# Cing_MainBoard.net
KiCad netlist of a schematic drawn in EAGLE
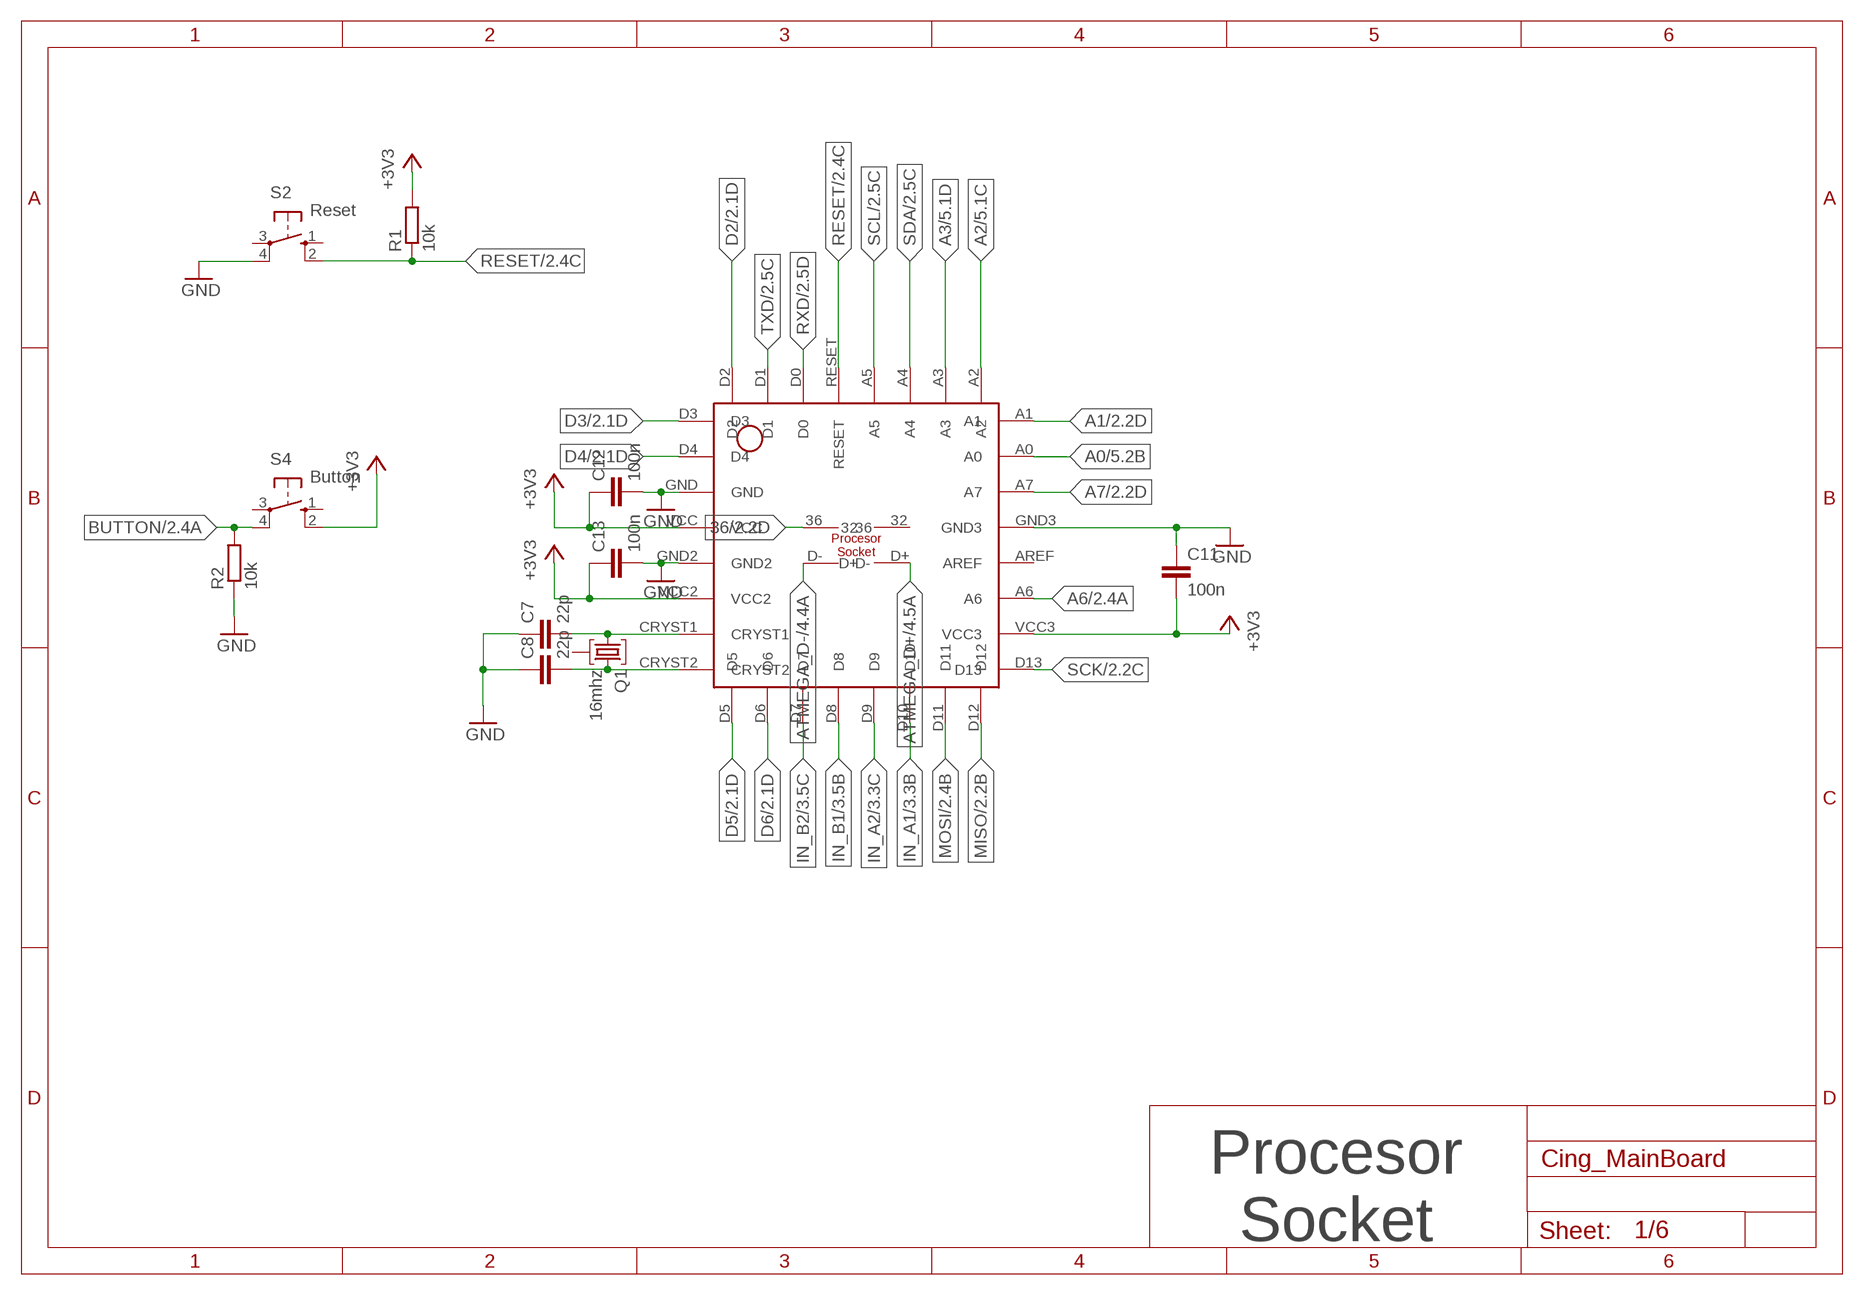
[diagram p0: schematic, sheet 1]
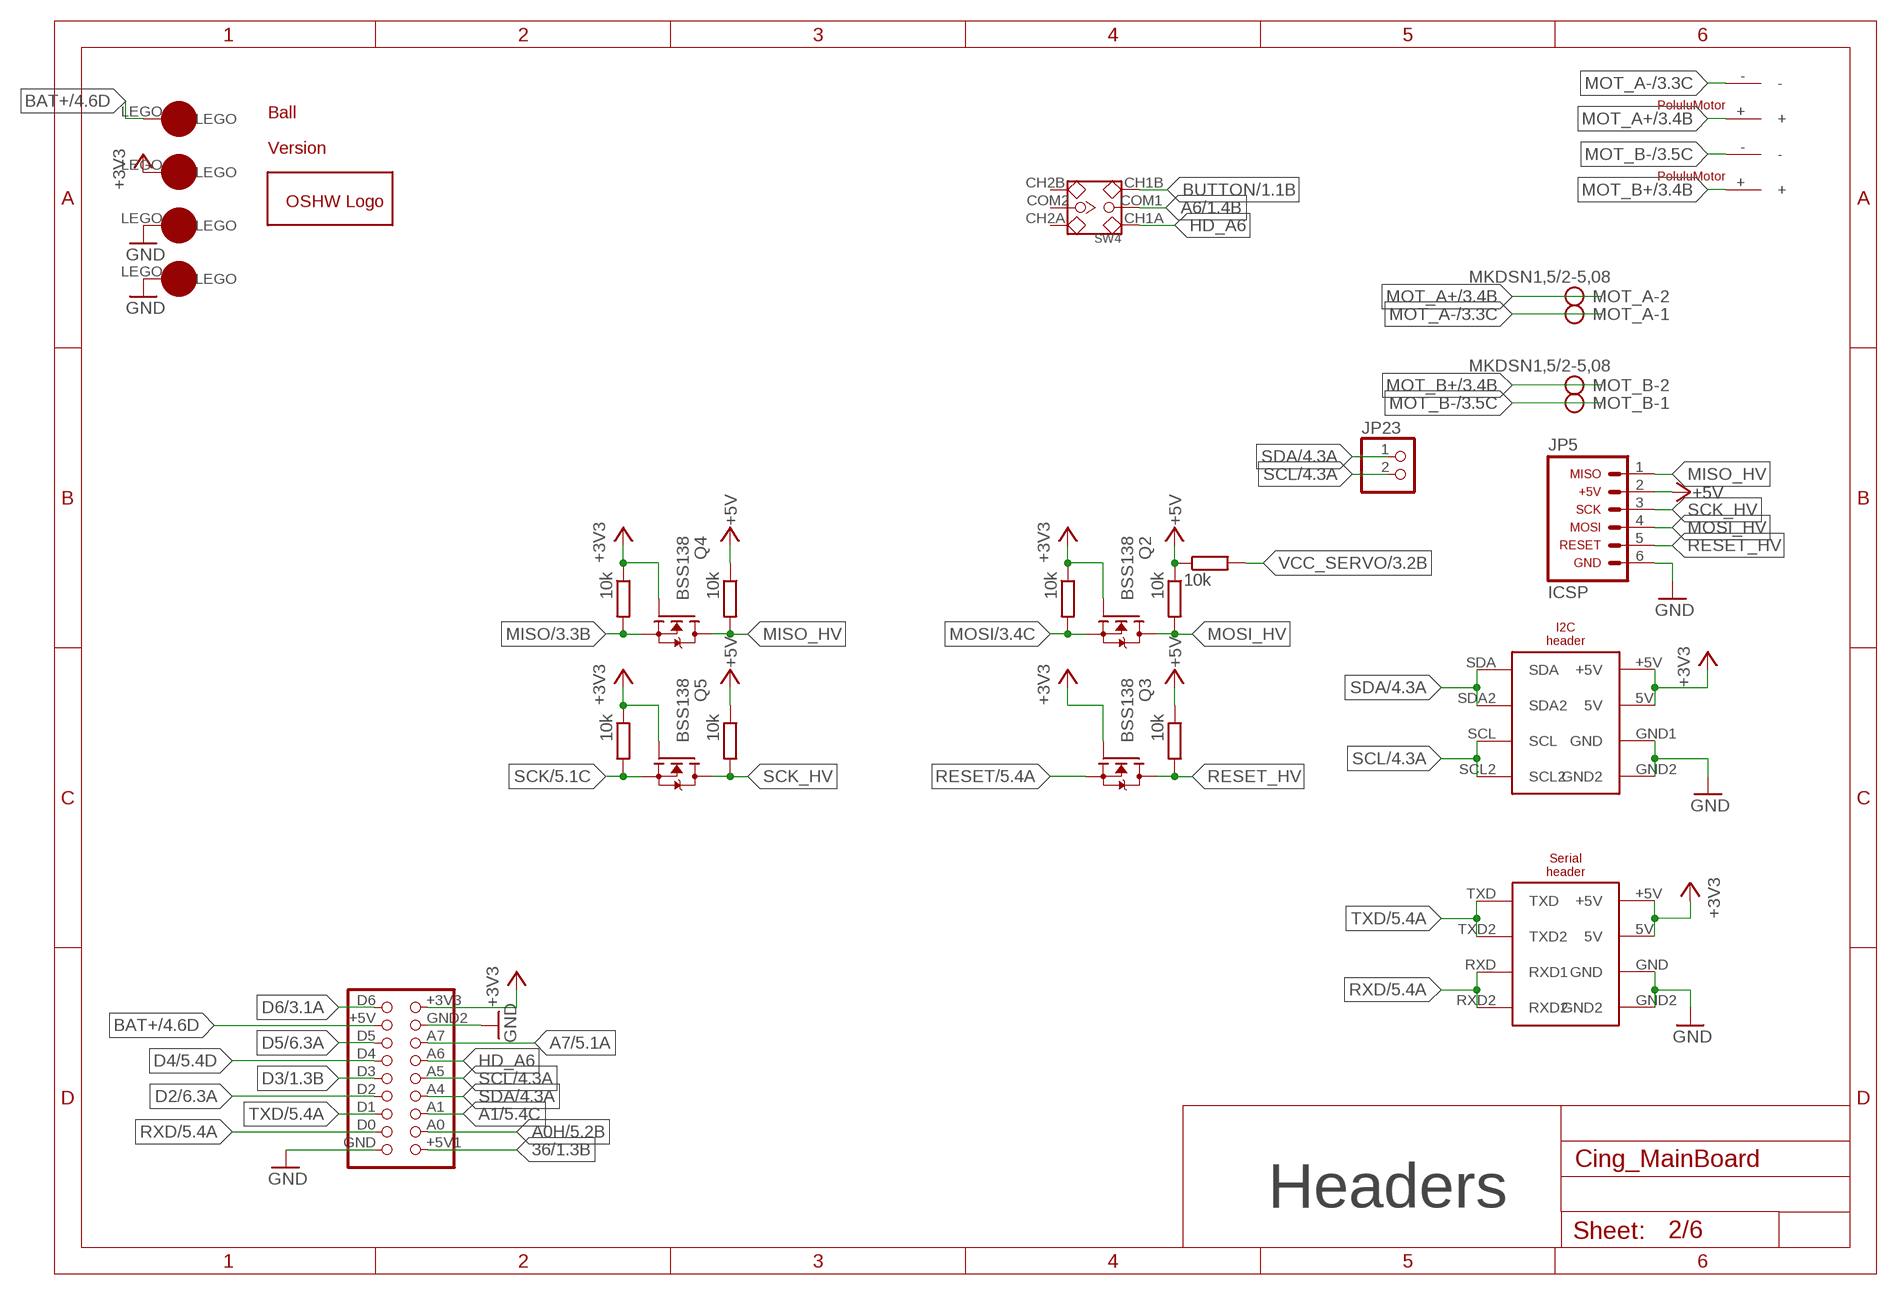
[diagram p1: schematic, sheet 2]
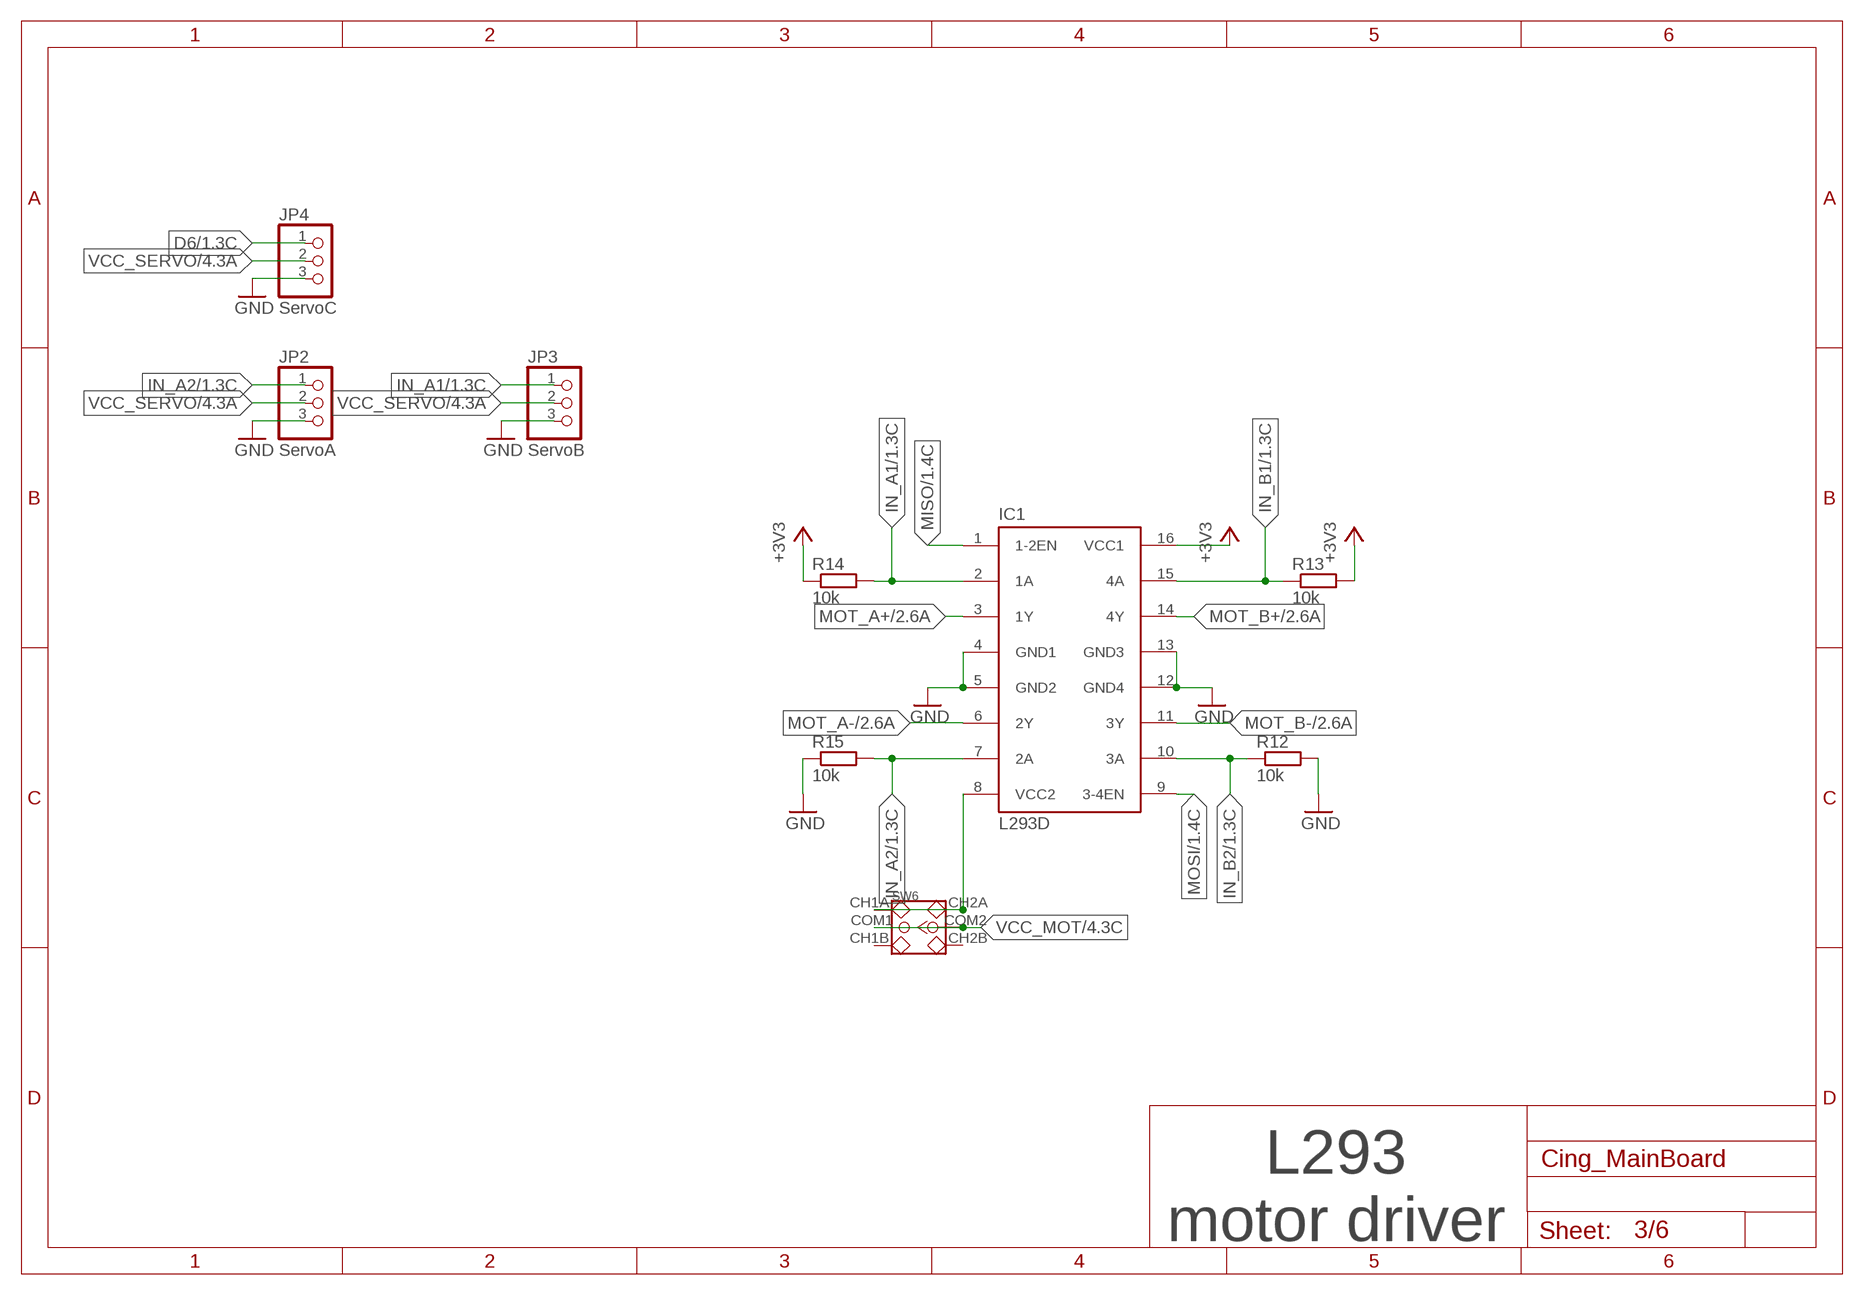
[diagram p2: schematic, sheet 3]
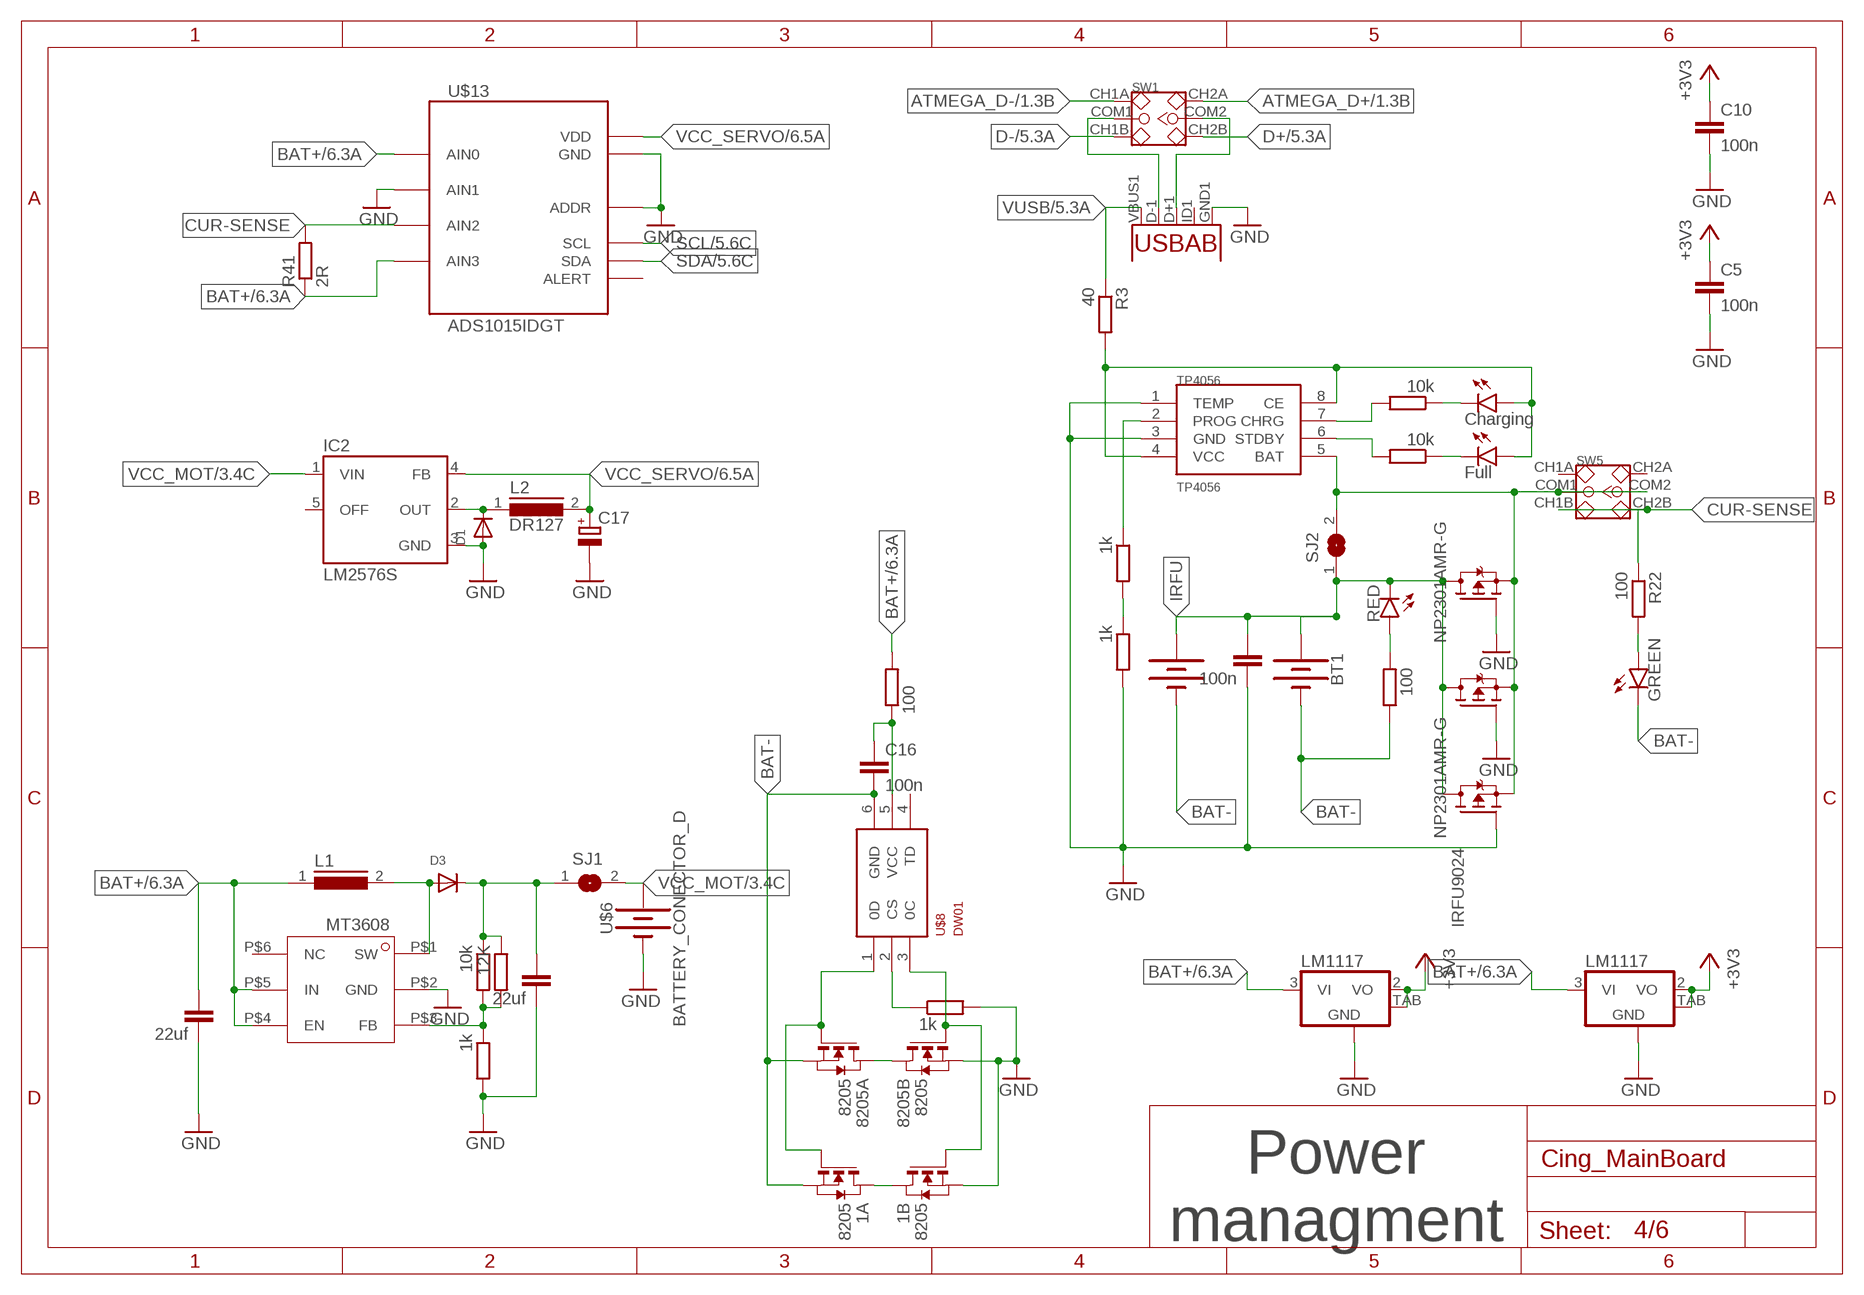
[diagram p3: schematic, sheet 4]
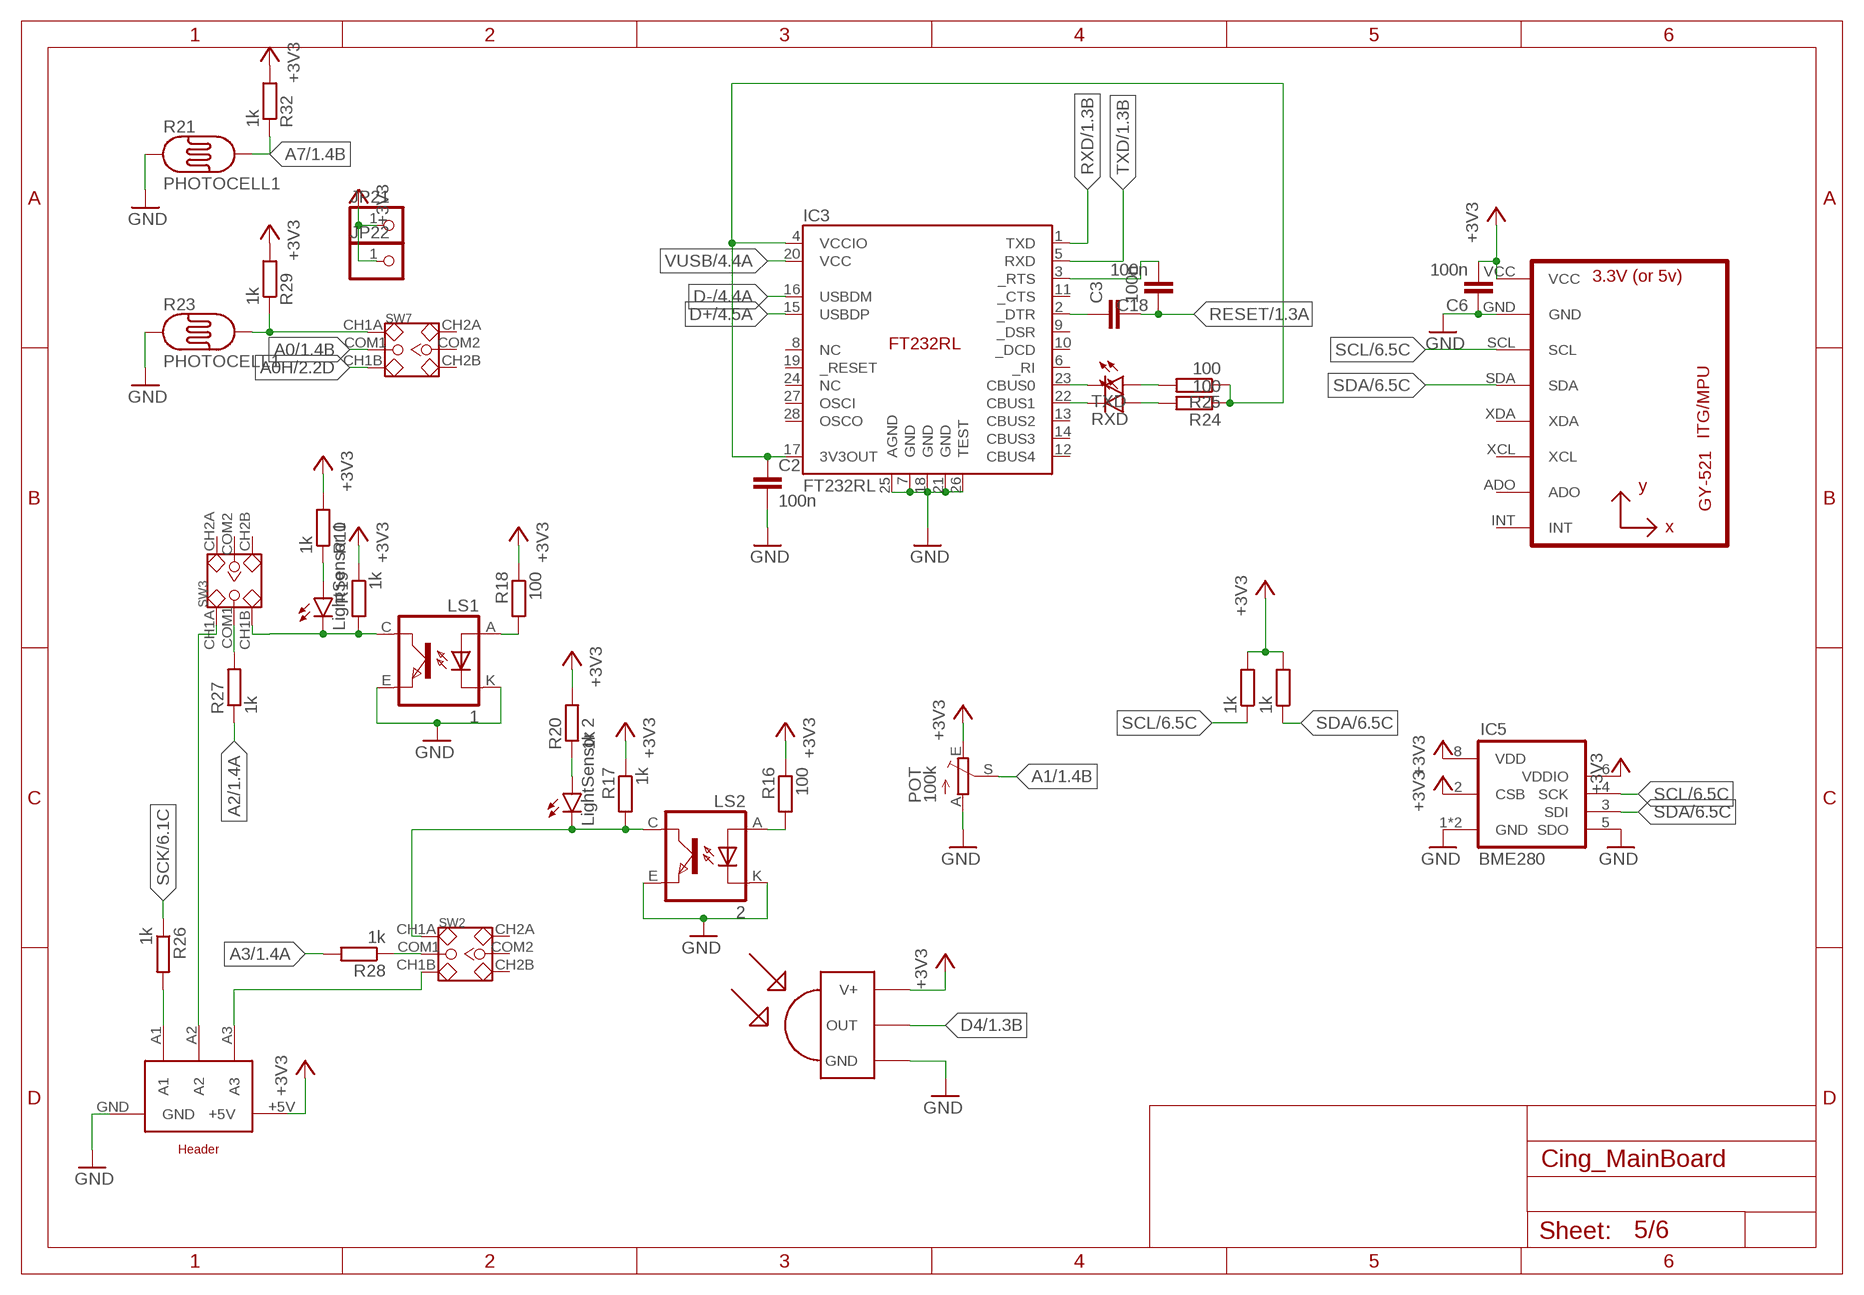
[diagram p4: schematic, sheet 5]
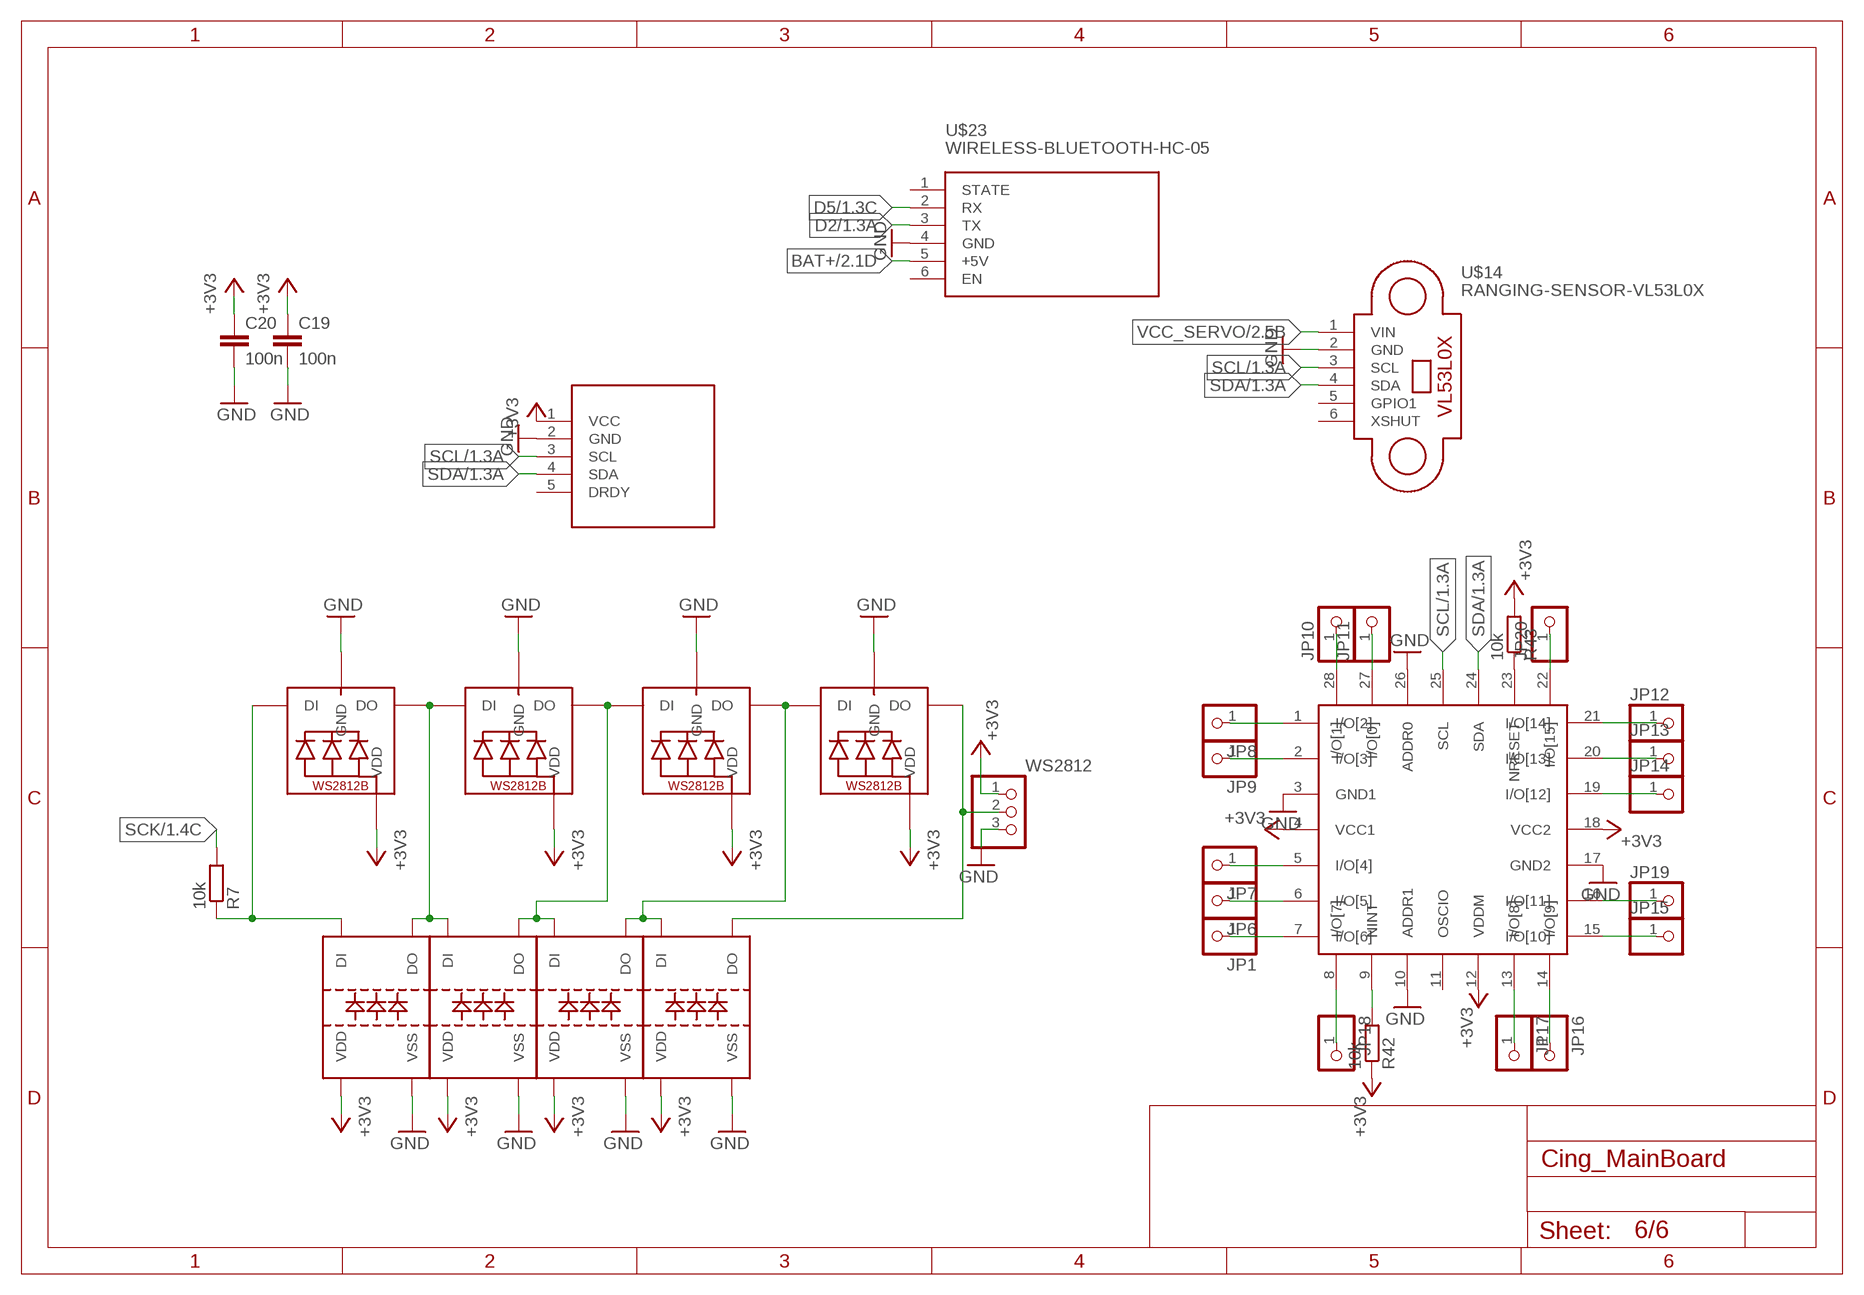
[diagram p5: schematic, sheet 6]

(export (version "E")
  (design (tool "Eeschema 10.0.6"))
  (components
    (comp (ref "IC1")
      (value "L293D")
      (footprint "eagle-import:L293")
      (libsource (lib "eagle-import") (part "L293D"))
    )
    (comp (ref "JP2")
      (value "ServoA")
      (footprint "eagle-import:1X03")
      (libsource (lib "eagle-import") (part "PINHD-1X3"))
    )
    (comp (ref "JP3")
      (value "ServoB")
      (footprint "eagle-import:1X03")
      (libsource (lib "eagle-import") (part "PINHD-1X3"))
    )
    (comp (ref "JP4")
      (value "ServoC")
      (footprint "eagle-import:1X03")
      (libsource (lib "eagle-import") (part "PINHD-1X3"))
    )
    (comp (ref "R12")
      (value "10k")
      (footprint "eagle-import:R1206")
      (libsource (lib "eagle-import") (part "R-EU_R1206"))
    )
    (comp (ref "R13")
      (value "10k")
      (footprint "eagle-import:R1206")
      (libsource (lib "eagle-import") (part "R-EU_R1206"))
    )
    (comp (ref "R14")
      (value "10k")
      (footprint "eagle-import:R1206")
      (libsource (lib "eagle-import") (part "R-EU_R1206"))
    )
    (comp (ref "R15")
      (value "10k")
      (footprint "eagle-import:R1206")
      (libsource (lib "eagle-import") (part "R-EU_R1206"))
    )
    (comp (ref "SW6")
      (value "USB_SWITCH")
      (footprint "eagle-import:USB_SWITCH")
      (libsource (lib "eagle-import") (part "USB_SWITCH"))
    )
    (comp (ref "JP5")
      (value "ICSP")
      (footprint "eagle-import:ICSP_HEADER")
      (libsource (lib "eagle-import") (part "ICSP_HEADER"))
    )
    (comp (ref "JP23")
      (value "PINHD-1X2")
      (footprint "eagle-import:1X02")
      (libsource (lib "eagle-import") (part "PINHD-1X2"))
    )
    (comp (ref "MOT_A")
      (value "MKDSN1,5/2-5,08")
      (footprint "eagle-import:MKDSN1,5_2-5,08")
      (libsource (lib "eagle-import") (part "MKDSN1,5/2-5,08"))
    )
    (comp (ref "MOT_B")
      (value "MKDSN1,5/2-5,08")
      (footprint "eagle-import:MKDSN1,5_2-5,08")
      (libsource (lib "eagle-import") (part "MKDSN1,5/2-5,08"))
    )
    (comp (ref "Q2")
      (value "BSS138")
      (footprint "eagle-import:SOT23")
      (fields (field (name "MF") "Fairchild"))
      (libsource (lib "eagle-import") (part "BSS138"))
    )
    (comp (ref "Q3")
      (value "BSS138")
      (footprint "eagle-import:SOT23")
      (fields (field (name "MF") "Fairchild"))
      (libsource (lib "eagle-import") (part "BSS138"))
    )
    (comp (ref "Q4")
      (value "BSS138")
      (footprint "eagle-import:SOT23")
      (fields (field (name "MF") "Fairchild"))
      (libsource (lib "eagle-import") (part "BSS138"))
    )
    (comp (ref "Q5")
      (value "BSS138")
      (footprint "eagle-import:SOT23")
      (fields (field (name "MF") "Fairchild"))
      (libsource (lib "eagle-import") (part "BSS138"))
    )
    (comp (ref "R33")
      (value "10k")
      (footprint "eagle-import:R1206")
      (libsource (lib "eagle-import") (part "R-EU_R1206"))
    )
    (comp (ref "R34")
      (value "10k")
      (footprint "eagle-import:R1206")
      (libsource (lib "eagle-import") (part "R-EU_R1206"))
    )
    (comp (ref "R35")
      (value "10k")
      (footprint "eagle-import:R1206")
      (libsource (lib "eagle-import") (part "R-EU_R1206"))
    )
    (comp (ref "R37")
      (value "10k")
      (footprint "eagle-import:R1206")
      (libsource (lib "eagle-import") (part "R-EU_R1206"))
    )
    (comp (ref "R38")
      (value "10k")
      (footprint "eagle-import:R1206")
      (libsource (lib "eagle-import") (part "R-EU_R1206"))
    )
    (comp (ref "R39")
      (value "10k")
      (footprint "eagle-import:R1206")
      (libsource (lib "eagle-import") (part "R-EU_R1206"))
    )
    (comp (ref "R40")
      (value "10k")
      (footprint "eagle-import:R1206")
      (libsource (lib "eagle-import") (part "R-EU_R1206"))
    )
    (comp (ref "R44")
      (value "10k")
      (footprint "eagle-import:R1206")
      (libsource (lib "eagle-import") (part "R-EU_R1206"))
    )
    (comp (ref "SW4")
      (value "USB_SWITCH")
      (footprint "eagle-import:USB_SWITCH")
      (libsource (lib "eagle-import") (part "USB_SWITCH"))
    )
    (comp (ref "U$2")
      (value "Header 2")
      (footprint "eagle-import:BIG_HEADER")
      (libsource (lib "eagle-import") (part "BIG_HEADER"))
    )
    (comp (ref "U$3")
      (value "I2C_HEADER")
      (footprint "eagle-import:I2_HEADER")
      (libsource (lib "eagle-import") (part "I2C_HEADER"))
    )
    (comp (ref "U$4")
      (value "SERIAL_HEADER")
      (footprint "eagle-import:SERIAL_HEADER")
      (libsource (lib "eagle-import") (part "SERIAL_HEADER"))
    )
    (comp (ref "U$9")
      (value "POLULU_MOTOR")
      (footprint "eagle-import:POLULU_MOTOR")
      (libsource (lib "eagle-import") (part "POLULU_MOTOR"))
    )
    (comp (ref "U$16")
      (value "BAT+")
      (footprint "eagle-import:LEGO-1X1")
      (libsource (lib "eagle-import") (part "LEGO-1X1"))
    )
    (comp (ref "U$17")
      (value "3.3V")
      (footprint "eagle-import:LEGO-1X1")
      (libsource (lib "eagle-import") (part "LEGO-1X1"))
    )
    (comp (ref "U$18")
      (value "GND")
      (footprint "eagle-import:LEGO-1X1")
      (libsource (lib "eagle-import") (part "LEGO-1X1"))
    )
    (comp (ref "U$19")
      (value "GND")
      (footprint "eagle-import:LEGO-1X1")
      (libsource (lib "eagle-import") (part "LEGO-1X1"))
    )
    (comp (ref "U$20")
      (value "BALL")
      (footprint "eagle-import:BALL")
      (libsource (lib "eagle-import") (part "BALL"))
    )
    (comp (ref "U$22")
      (value "OPENSOURCE")
      (footprint "eagle-import:OSHW_5MM")
      (libsource (lib "eagle-import") (part "OPENSOURCE"))
    )
    (comp (ref "U$24")
      (value "POLULU_MOTOR")
      (footprint "eagle-import:POLULU_MOTOR")
      (libsource (lib "eagle-import") (part "POLULU_MOTOR"))
    )
    (comp (ref "VERSION")
      (value "3.1")
      (footprint "eagle-import:VERSION")
      (libsource (lib "eagle-import") (part "VERSION"))
    )
    (comp (ref "C7")
      (value "22p")
      (footprint "eagle-import:C1206")
      (libsource (lib "eagle-import") (part "C-EUC1206"))
    )
    (comp (ref "C8")
      (value "22p")
      (footprint "eagle-import:C1206")
      (libsource (lib "eagle-import") (part "C-EUC1206"))
    )
    (comp (ref "C11")
      (value "100n")
      (footprint "eagle-import:C1206")
      (libsource (lib "eagle-import") (part "C-EUC1206"))
    )
    (comp (ref "C12")
      (value "100n")
      (footprint "eagle-import:C1206")
      (libsource (lib "eagle-import") (part "C-EUC1206"))
    )
    (comp (ref "C13")
      (value "100n")
      (footprint "eagle-import:C1206")
      (libsource (lib "eagle-import") (part "C-EUC1206"))
    )
    (comp (ref "Q1")
      (value "16mhz")
      (footprint "eagle-import:HC49U")
      (libsource (lib "eagle-import") (part "12M10AHC49HT"))
    )
    (comp (ref "R1")
      (value "10k")
      (footprint "eagle-import:R1206")
      (libsource (lib "eagle-import") (part "R-EU_R1206"))
    )
    (comp (ref "R2")
      (value "10k")
      (footprint "eagle-import:R1206")
      (libsource (lib "eagle-import") (part "R-EU_R1206"))
    )
    (comp (ref "S2")
      (value "Reset")
      (footprint "eagle-import:B3F-10XX")
      (fields (field (name "MPN") "B3F-1000"))
      (libsource (lib "eagle-import") (part "10-XX"))
    )
    (comp (ref "S4")
      (value "Button")
      (footprint "eagle-import:B3F-10XX")
      (fields (field (name "MPN") "B3F-1000"))
      (libsource (lib "eagle-import") (part "10-XX"))
    )
    (comp (ref "U$1")
      (value "PROCESSOR-SOCKET_PCB")
      (footprint "eagle-import:PROCESSOR-SOCKET_PCB")
      (libsource (lib "eagle-import") (part "PROCESSOR-SOCKET_PCB"))
    )
    (comp (ref "1")
      (value "8205")
      (footprint "eagle-import:TSSOP-8")
      (libsource (lib "eagle-import") (part "DMN3024LSD"))
    )
    (comp (ref "8205")
      (value "8205")
      (footprint "eagle-import:TSSOP-8")
      (libsource (lib "eagle-import") (part "DMN3024LSD"))
    )
    (comp (ref "BT1")
      (value "BATTERY-AA_KIT")
      (footprint "eagle-import:BATTERY-AA-KIT")
      (libsource (lib "eagle-import") (part "BATTERY-AA_KIT"))
    )
    (comp (ref "C1")
      (value "100n")
      (footprint "eagle-import:C1206")
      (libsource (lib "eagle-import") (part "C-EUC1206"))
    )
    (comp (ref "C5")
      (value "100n")
      (footprint "eagle-import:C1206")
      (libsource (lib "eagle-import") (part "C-EUC1206"))
    )
    (comp (ref "C10")
      (value "100n")
      (footprint "eagle-import:C1206")
      (libsource (lib "eagle-import") (part "C-EUC1206"))
    )
    (comp (ref "C14")
      (value "22uf")
      (footprint "eagle-import:C1206")
      (libsource (lib "eagle-import") (part "C-EUC1206"))
    )
    (comp (ref "C15")
      (value "22uf")
      (footprint "eagle-import:C1206")
      (libsource (lib "eagle-import") (part "C-EUC1206"))
    )
    (comp (ref "C16")
      (value "100n")
      (footprint "eagle-import:C1206")
      (libsource (lib "eagle-import") (part "C-EUC1206"))
    )
    (comp (ref "C17")
      (value "CPOL-EUE3.5-8")
      (footprint "eagle-import:E3,5-8")
      (libsource (lib "eagle-import") (part "CPOL-EUE3.5-8"))
    )
    (comp (ref "D1")
      (value "DIODESMA")
      (footprint "eagle-import:SMADIODE")
      (libsource (lib "eagle-import") (part "DIODESMA"))
    )
    (comp (ref "D3")
      (value "DIODESMA")
      (footprint "eagle-import:SMADIODE")
      (libsource (lib "eagle-import") (part "DIODESMA"))
    )
    (comp (ref "IC2")
      (value "LM2576S")
      (footprint "eagle-import:TO263-5")
      (libsource (lib "eagle-import") (part "LM2576S"))
    )
    (comp (ref "IRFU9024")
      (value "IRFU9024")
      (footprint "eagle-import:IRFU9024")
      (libsource (lib "eagle-import") (part "IRFU9024"))
    )
    (comp (ref "L1")
      (value "DR125")
      (footprint "eagle-import:DR125")
      (libsource (lib "eagle-import") (part "DR125"))
    )
    (comp (ref "L2")
      (value "DR127")
      (footprint "eagle-import:DR127")
      (libsource (lib "eagle-import") (part "DR127"))
    )
    (comp (ref "LED1")
      (value "Charging")
      (footprint "eagle-import:1206")
      (libsource (lib "eagle-import") (part "LEDSMT1206"))
    )
    (comp (ref "ON")
      (value "GREEN")
      (footprint "eagle-import:1206")
      (libsource (lib "eagle-import") (part "LEDSMT1206"))
    )
    (comp (ref "Q6")
      (value "NP2301AMR-G")
      (footprint "eagle-import:SC75_INFINEON")
      (libsource (lib "eagle-import") (part "BSA223SP"))
    )
    (comp (ref "Q7")
      (value "NP2301AMR-G")
      (footprint "eagle-import:SC75_INFINEON")
      (libsource (lib "eagle-import") (part "BSA223SP"))
    )
    (comp (ref "R3")
      (value "40")
      (footprint "eagle-import:R1206")
      (libsource (lib "eagle-import") (part "R-EU_R1206"))
    )
    (comp (ref "R4")
      (value "1k")
      (footprint "eagle-import:R1206")
      (libsource (lib "eagle-import") (part "R-EU_R1206"))
    )
    (comp (ref "R5")
      (value "10k")
      (footprint "eagle-import:R1206")
      (libsource (lib "eagle-import") (part "R-EU_R1206"))
    )
    (comp (ref "R6")
      (value "100")
      (footprint "eagle-import:R1206")
      (libsource (lib "eagle-import") (part "R-EU_R1206"))
    )
    (comp (ref "R8")
      (value "1k")
      (footprint "eagle-import:R1206")
      (libsource (lib "eagle-import") (part "R-EU_R1206"))
    )
    (comp (ref "R9")
      (value "10k")
      (footprint "eagle-import:R1206")
      (libsource (lib "eagle-import") (part "R-EU_R1206"))
    )
    (comp (ref "R11")
      (value "10k")
      (footprint "eagle-import:R1206")
      (libsource (lib "eagle-import") (part "R-EU_R1206"))
    )
    (comp (ref "R22")
      (value "100")
      (footprint "eagle-import:R1206")
      (libsource (lib "eagle-import") (part "R-EU_R1206"))
    )
    (comp (ref "R41")
      (value "2R")
      (footprint "eagle-import:R2512")
      (libsource (lib "eagle-import") (part "R-EU_R2512"))
    )
    (comp (ref "R46")
      (value "1k")
      (footprint "eagle-import:R1206")
      (libsource (lib "eagle-import") (part "R-EU_R1206"))
    )
    (comp (ref "R47")
      (value "1k")
      (footprint "eagle-import:R1206")
      (libsource (lib "eagle-import") (part "R-EU_R1206"))
    )
    (comp (ref "R48")
      (value "100")
      (footprint "eagle-import:R1206")
      (libsource (lib "eagle-import") (part "R-EU_R1206"))
    )
    (comp (ref "R49")
      (value "12K")
      (footprint "eagle-import:R1206")
      (libsource (lib "eagle-import") (part "R-EU_R1206"))
    )
    (comp (ref "REVERSE")
      (value "RED")
      (footprint "eagle-import:1206")
      (libsource (lib "eagle-import") (part "LEDSMT1206"))
    )
    (comp (ref "SJ1")
      (value "SJW")
      (footprint "eagle-import:SJW")
      (libsource (lib "eagle-import") (part "SJW"))
    )
    (comp (ref "SJ2") (value "SJ") (footprint "eagle-import:SJ") (libsource (lib "eagle-import") (part "SJ")))
    (comp (ref "SW1")
      (value "USB_SWITCH")
      (footprint "eagle-import:USB_SWITCH")
      (libsource (lib "eagle-import") (part "USB_SWITCH"))
    )
    (comp (ref "SW5")
      (value "USB_SWITCH")
      (footprint "eagle-import:USB_SWITCH")
      (libsource (lib "eagle-import") (part "USB_SWITCH"))
    )
    (comp (ref "TP4056")
      (value "TP4056")
      (footprint "eagle-import:TP4056")
      (libsource (lib "eagle-import") (part "TP4056"))
    )
    (comp (ref "U$5")
      (value "MT3608SOT23-6")
      (footprint "eagle-import:SOT23-6")
      (libsource (lib "eagle-import") (part "MT3608SOT23-6"))
    )
    (comp (ref "U$6")
      (value "BATTERY_CONECTOR_D")
      (footprint "eagle-import:BATTERY_CONECTOR_D")
      (libsource (lib "eagle-import") (part "BATTERY_CONECTOR_D"))
    )
    (comp (ref "U$7")
      (value "BATTERY_CONECTOR_D")
      (footprint "eagle-import:BATTERY_CONECTOR_D")
      (libsource (lib "eagle-import") (part "BATTERY_CONECTOR_D"))
    )
    (comp (ref "U$8")
      (value "DW01")
      (footprint "eagle-import:SOT23-6")
      (libsource (lib "eagle-import") (part "DW01"))
    )
    (comp (ref "U$10")
      (value "LM1117")
      (footprint "eagle-import:LM1117")
      (libsource (lib "eagle-import") (part "LM1117"))
    )
    (comp (ref "U$11")
      (value "LM1117")
      (footprint "eagle-import:LM1117")
      (libsource (lib "eagle-import") (part "LM1117"))
    )
    (comp (ref "U$13")
      (value "ADS1015IDGT")
      (footprint "eagle-import:MSOP10_0.5")
      (libsource (lib "eagle-import") (part "ADS1015IDGT"))
    )
    (comp (ref "U1")
      (value "MICRO_USB\"\"")
      (footprint "eagle-import:USB-MICRO-SMD")
      (libsource (lib "eagle-import") (part "MICRO_USB{dblquote}{dblquote}"))
    )
    (comp (ref "YELLOW")
      (value "Full")
      (footprint "eagle-import:1206")
      (libsource (lib "eagle-import") (part "LEDSMT1206"))
    )
    (comp (ref "C2")
      (value "100n")
      (footprint "eagle-import:C1206")
      (libsource (lib "eagle-import") (part "C-EUC1206"))
    )
    (comp (ref "C3")
      (value "100n")
      (footprint "eagle-import:C1206")
      (libsource (lib "eagle-import") (part "C-EUC1206"))
    )
    (comp (ref "C6")
      (value "100n")
      (footprint "eagle-import:C1206")
      (libsource (lib "eagle-import") (part "C-EUC1206"))
    )
    (comp (ref "C18")
      (value "100n")
      (footprint "eagle-import:C1206")
      (libsource (lib "eagle-import") (part "C-EUC1206"))
    )
    (comp (ref "IC3")
      (value "FT232RL")
      (footprint "eagle-import:FT232RL")
      (libsource (lib "eagle-import") (part "FT232RL"))
    )
    (comp (ref "IC5")
      (value "BME280")
      (footprint "eagle-import:BME280")
      (libsource (lib "eagle-import") (part "BME280"))
    )
    (comp (ref "JP21")
      (value "PINHD-1X1")
      (footprint "eagle-import:1X01")
      (libsource (lib "eagle-import") (part "PINHD-1X1"))
    )
    (comp (ref "JP22")
      (value "PINHD-1X1")
      (footprint "eagle-import:1X01")
      (libsource (lib "eagle-import") (part "PINHD-1X1"))
    )
    (comp (ref "LED3")
      (value "RXD")
      (footprint "eagle-import:1206")
      (libsource (lib "eagle-import") (part "LEDSMT1206"))
    )
    (comp (ref "LS1")
      (value "1")
      (footprint "eagle-import:TCRT5000")
      (libsource (lib "eagle-import") (part "TCRT5000"))
    )
    (comp (ref "LS2")
      (value "2")
      (footprint "eagle-import:TCRT5000")
      (libsource (lib "eagle-import") (part "TCRT5000"))
    )
    (comp (ref "POT")
      (value "100k")
      (footprint "eagle-import:RJ9W")
      (libsource (lib "eagle-import") (part "TRIM_EU-RJ9W"))
    )
    (comp (ref "R10")
      (value "1k")
      (footprint "eagle-import:R1206")
      (libsource (lib "eagle-import") (part "R-EU_R1206"))
    )
    (comp (ref "R16")
      (value "100")
      (footprint "eagle-import:R1206")
      (libsource (lib "eagle-import") (part "R-EU_R1206"))
    )
    (comp (ref "R17")
      (value "1k")
      (footprint "eagle-import:R1206")
      (libsource (lib "eagle-import") (part "R-EU_R1206"))
    )
    (comp (ref "R18")
      (value "100")
      (footprint "eagle-import:R1206")
      (libsource (lib "eagle-import") (part "R-EU_R1206"))
    )
    (comp (ref "R19")
      (value "1k")
      (footprint "eagle-import:R1206")
      (libsource (lib "eagle-import") (part "R-EU_R1206"))
    )
    (comp (ref "R20")
      (value "1k")
      (footprint "eagle-import:R1206")
      (libsource (lib "eagle-import") (part "R-EU_R1206"))
    )
    (comp (ref "R21")
      (value "PHOTOCELL1")
      (footprint "eagle-import:LDR_OFFBOARD")
      (libsource (lib "eagle-import") (part "PHOTOCELL1"))
    )
    (comp (ref "R23")
      (value "PHOTOCELL1")
      (footprint "eagle-import:LDR_OFFBOARD")
      (libsource (lib "eagle-import") (part "PHOTOCELL1"))
    )
    (comp (ref "R24")
      (value "100")
      (footprint "eagle-import:R1206")
      (libsource (lib "eagle-import") (part "R-EU_R1206"))
    )
    (comp (ref "R25")
      (value "100")
      (footprint "eagle-import:R1206")
      (libsource (lib "eagle-import") (part "R-EU_R1206"))
    )
    (comp (ref "R26")
      (value "1k")
      (footprint "eagle-import:R1206")
      (libsource (lib "eagle-import") (part "R-EU_R1206"))
    )
    (comp (ref "R27")
      (value "1k")
      (footprint "eagle-import:R1206")
      (libsource (lib "eagle-import") (part "R-EU_R1206"))
    )
    (comp (ref "R28")
      (value "1k")
      (footprint "eagle-import:R1206")
      (libsource (lib "eagle-import") (part "R-EU_R1206"))
    )
    (comp (ref "R29")
      (value "1k")
      (footprint "eagle-import:R1206")
      (libsource (lib "eagle-import") (part "R-EU_R1206"))
    )
    (comp (ref "R30")
      (value "1k")
      (footprint "eagle-import:R1206")
      (libsource (lib "eagle-import") (part "R-EU_R1206"))
    )
    (comp (ref "R31")
      (value "1k")
      (footprint "eagle-import:R1206")
      (libsource (lib "eagle-import") (part "R-EU_R1206"))
    )
    (comp (ref "R32")
      (value "1k")
      (footprint "eagle-import:R1206")
      (libsource (lib "eagle-import") (part "R-EU_R1206"))
    )
    (comp (ref "SW2")
      (value "USB_SWITCH")
      (footprint "eagle-import:USB_SWITCH")
      (libsource (lib "eagle-import") (part "USB_SWITCH"))
    )
    (comp (ref "SW3")
      (value "USB_SWITCH")
      (footprint "eagle-import:USB_SWITCH")
      (libsource (lib "eagle-import") (part "USB_SWITCH"))
    )
    (comp (ref "SW7")
      (value "USB_SWITCH")
      (footprint "eagle-import:USB_SWITCH")
      (libsource (lib "eagle-import") (part "USB_SWITCH"))
    )
    (comp (ref "TSOP4838")
      (value "TSOP4838")
      (footprint "eagle-import:TSOP18XX")
      (libsource (lib "eagle-import") (part "TSOP4838"))
    )
    (comp (ref "TXD")
      (value "TXD")
      (footprint "eagle-import:1206")
      (libsource (lib "eagle-import") (part "LEDSMT1206"))
    )
    (comp (ref "TXD1")
      (value "LightSensor 1")
      (footprint "eagle-import:1206")
      (libsource (lib "eagle-import") (part "LEDSMT1206"))
    )
    (comp (ref "TXD2")
      (value "LightSensor 2")
      (footprint "eagle-import:1206")
      (libsource (lib "eagle-import") (part "LEDSMT1206"))
    )
    (comp (ref "U$12")
      (value "CONNECTOR_1X5")
      (footprint "eagle-import:CONNECTOR_1X5")
      (libsource (lib "eagle-import") (part "CONNECTOR_1X5"))
    )
    (comp (ref "U3")
      (value "MPU-6050MPU6050")
      (footprint "eagle-import:MPU-6050")
      (libsource (lib "eagle-import") (part "MPU-6050MPU6050"))
    )
    (comp (ref "C19")
      (value "100n")
      (footprint "eagle-import:C1206")
      (libsource (lib "eagle-import") (part "C-EUC1206"))
    )
    (comp (ref "C20")
      (value "100n")
      (footprint "eagle-import:C1206")
      (libsource (lib "eagle-import") (part "C-EUC1206"))
    )
    (comp (ref "JP1")
      (value "PINHD-1X1")
      (footprint "eagle-import:1X01")
      (libsource (lib "eagle-import") (part "PINHD-1X1"))
    )
    (comp (ref "JP6")
      (value "PINHD-1X1")
      (footprint "eagle-import:1X01")
      (libsource (lib "eagle-import") (part "PINHD-1X1"))
    )
    (comp (ref "JP7")
      (value "PINHD-1X1")
      (footprint "eagle-import:1X01")
      (libsource (lib "eagle-import") (part "PINHD-1X1"))
    )
    (comp (ref "JP8")
      (value "PINHD-1X1")
      (footprint "eagle-import:1X01")
      (libsource (lib "eagle-import") (part "PINHD-1X1"))
    )
    (comp (ref "JP9")
      (value "PINHD-1X1")
      (footprint "eagle-import:1X01")
      (libsource (lib "eagle-import") (part "PINHD-1X1"))
    )
    (comp (ref "JP10")
      (value "PINHD-1X1")
      (footprint "eagle-import:1X01")
      (libsource (lib "eagle-import") (part "PINHD-1X1"))
    )
    (comp (ref "JP11")
      (value "PINHD-1X1")
      (footprint "eagle-import:1X01")
      (libsource (lib "eagle-import") (part "PINHD-1X1"))
    )
    (comp (ref "JP12")
      (value "PINHD-1X1")
      (footprint "eagle-import:1X01")
      (libsource (lib "eagle-import") (part "PINHD-1X1"))
    )
    (comp (ref "JP13")
      (value "PINHD-1X1")
      (footprint "eagle-import:1X01")
      (libsource (lib "eagle-import") (part "PINHD-1X1"))
    )
    (comp (ref "JP14")
      (value "PINHD-1X1")
      (footprint "eagle-import:1X01")
      (libsource (lib "eagle-import") (part "PINHD-1X1"))
    )
    (comp (ref "JP15")
      (value "PINHD-1X1")
      (footprint "eagle-import:1X01")
      (libsource (lib "eagle-import") (part "PINHD-1X1"))
    )
    (comp (ref "JP16")
      (value "PINHD-1X1")
      (footprint "eagle-import:1X01")
      (libsource (lib "eagle-import") (part "PINHD-1X1"))
    )
    (comp (ref "JP17")
      (value "PINHD-1X1")
      (footprint "eagle-import:1X01")
      (libsource (lib "eagle-import") (part "PINHD-1X1"))
    )
    (comp (ref "JP18")
      (value "PINHD-1X1")
      (footprint "eagle-import:1X01")
      (libsource (lib "eagle-import") (part "PINHD-1X1"))
    )
    (comp (ref "JP19")
      (value "PINHD-1X1")
      (footprint "eagle-import:1X01")
      (libsource (lib "eagle-import") (part "PINHD-1X1"))
    )
    (comp (ref "JP20")
      (value "PINHD-1X1")
      (footprint "eagle-import:1X01")
      (libsource (lib "eagle-import") (part "PINHD-1X1"))
    )
    (comp (ref "LED4")
      (value "WS2812B3535")
      (footprint "eagle-import:LED3535")
      (libsource (lib "eagle-import") (part "WS2812B3535"))
    )
    (comp (ref "LED5")
      (value "WS2812B")
      (footprint "eagle-import:WS2812B")
      (libsource (lib "eagle-import") (part "WS2812B"))
    )
    (comp (ref "LED6")
      (value "WS2812B")
      (footprint "eagle-import:WS2812B")
      (libsource (lib "eagle-import") (part "WS2812B"))
    )
    (comp (ref "LED7")
      (value "WS2812B")
      (footprint "eagle-import:WS2812B")
      (libsource (lib "eagle-import") (part "WS2812B"))
    )
    (comp (ref "LED8")
      (value "WS2812B")
      (footprint "eagle-import:WS2812B")
      (libsource (lib "eagle-import") (part "WS2812B"))
    )
    (comp (ref "LED9")
      (value "WS2812B3535")
      (footprint "eagle-import:LED3535")
      (libsource (lib "eagle-import") (part "WS2812B3535"))
    )
    (comp (ref "LED10")
      (value "WS2812B3535")
      (footprint "eagle-import:LED3535")
      (libsource (lib "eagle-import") (part "WS2812B3535"))
    )
    (comp (ref "LED11")
      (value "WS2812B3535")
      (footprint "eagle-import:LED3535")
      (libsource (lib "eagle-import") (part "WS2812B3535"))
    )
    (comp (ref "R7")
      (value "10k")
      (footprint "eagle-import:R1206")
      (libsource (lib "eagle-import") (part "R-EU_R1206"))
    )
    (comp (ref "R42")
      (value "10k")
      (footprint "eagle-import:R1206")
      (libsource (lib "eagle-import") (part "R-EU_R1206"))
    )
    (comp (ref "R43")
      (value "10k")
      (footprint "eagle-import:R1206")
      (libsource (lib "eagle-import") (part "R-EU_R1206"))
    )
    (comp (ref "U$14")
      (value "RANGING-SENSOR-VL53L0X")
      (footprint "eagle-import:RANGING-SENSOR-VL53L0X")
      (libsource (lib "eagle-import") (part "RANGING-SENSOR-VL53L0X"))
    )
    (comp (ref "U$15")
      (value "COMPASS-HMC5883L")
      (footprint "eagle-import:COMPASS-HMC5883L")
      (libsource (lib "eagle-import") (part "COMPASS-HMC5883L"))
    )
    (comp (ref "U$21")
      (value "SX1509")
      (footprint "eagle-import:QFN28")
      (libsource (lib "eagle-import") (part "SX1509"))
    )
    (comp (ref "U$23")
      (value "WIRELESS-BLUETOOTH-HC-05")
      (footprint "eagle-import:WIRELESS-BLUETOOTH-HC-05")
      (libsource (lib "eagle-import") (part "WIRELESS-BLUETOOTH-HC-05"))
    )
    (comp (ref "WS2812")
      (value "PINHD-1X3")
      (footprint "eagle-import:1X03")
      (libsource (lib "eagle-import") (part "PINHD-1X3"))
    )
  )
  (nets
    (net (code "1") (name "+3V3") (class "Default")
      (node (ref "C10") (pin "1") (pinfunction "1_1") (pintype "passive"))
      (node (ref "C11") (pin "2") (pinfunction "2_2") (pintype "passive"))
      (node (ref "C12") (pin "1") (pinfunction "1_1") (pintype "passive"))
      (node (ref "C13") (pin "1") (pinfunction "1_1") (pintype "passive"))
      (node (ref "C19") (pin "1") (pinfunction "1_1") (pintype "passive"))
      (node (ref "C20") (pin "1") (pinfunction "1_1") (pintype "passive"))
      (node (ref "C5") (pin "1") (pinfunction "1_1") (pintype "passive"))
      (node (ref "C6") (pin "2") (pinfunction "2_2") (pintype "passive"))
      (node (ref "IC1") (pin "16") (pinfunction "VCC1_16") (pintype "power_in"))
      (node (ref "IC5") (pin "2") (pinfunction "CSB_2") (pintype "input"))
      (node (ref "IC5") (pin "6") (pinfunction "VDDIO_6") (pintype "power_in"))
      (node (ref "IC5") (pin "8") (pinfunction "VDD_8") (pintype "power_in"))
      (node (ref "JP21") (pin "1") (pinfunction "1_1") (pintype "passive"))
      (node (ref "JP22") (pin "1") (pinfunction "1_1") (pintype "passive"))
      (node (ref "LED10") (pin "2") (pinfunction "VDD_2") (pintype "power_in"))
      (node (ref "LED11") (pin "2") (pinfunction "VDD_2") (pintype "power_in"))
      (node (ref "LED4") (pin "2") (pinfunction "VDD_2") (pintype "power_in"))
      (node (ref "LED5") (pin "1") (pinfunction "VDD_1") (pintype "bidirectional"))
      (node (ref "LED6") (pin "1") (pinfunction "VDD_1") (pintype "bidirectional"))
      (node (ref "LED7") (pin "1") (pinfunction "VDD_1") (pintype "bidirectional"))
      (node (ref "LED8") (pin "1") (pinfunction "VDD_1") (pintype "bidirectional"))
      (node (ref "LED9") (pin "2") (pinfunction "VDD_2") (pintype "power_in"))
      (node (ref "POT") (pin "E") (pinfunction "E_E") (pintype "passive"))
      (node (ref "Q2") (pin "1") (pinfunction "G_1") (pintype "passive"))
      (node (ref "Q3") (pin "1") (pinfunction "G_1") (pintype "passive"))
      (node (ref "Q4") (pin "1") (pinfunction "G_1") (pintype "passive"))
      (node (ref "Q5") (pin "1") (pinfunction "G_1") (pintype "passive"))
      (node (ref "R1") (pin "2") (pinfunction "2_2") (pintype "passive"))
      (node (ref "R10") (pin "2") (pinfunction "2_2") (pintype "passive"))
      (node (ref "R13") (pin "2") (pinfunction "2_2") (pintype "passive"))
      (node (ref "R14") (pin "1") (pinfunction "1_1") (pintype "passive"))
      (node (ref "R16") (pin "1") (pinfunction "1_1") (pintype "passive"))
      (node (ref "R17") (pin "1") (pinfunction "1_1") (pintype "passive"))
      (node (ref "R18") (pin "1") (pinfunction "1_1") (pintype "passive"))
      (node (ref "R19") (pin "1") (pinfunction "1_1") (pintype "passive"))
      (node (ref "R20") (pin "2") (pinfunction "2_2") (pintype "passive"))
      (node (ref "R29") (pin "2") (pinfunction "2_2") (pintype "passive"))
      (node (ref "R30") (pin "2") (pinfunction "2_2") (pintype "passive"))
      (node (ref "R31") (pin "2") (pinfunction "2_2") (pintype "passive"))
      (node (ref "R32") (pin "2") (pinfunction "2_2") (pintype "passive"))
      (node (ref "R34") (pin "1") (pinfunction "1_1") (pintype "passive"))
      (node (ref "R38") (pin "1") (pinfunction "1_1") (pintype "passive"))
      (node (ref "R40") (pin "1") (pinfunction "1_1") (pintype "passive"))
      (node (ref "R42") (pin "1") (pinfunction "1_1") (pintype "passive"))
      (node (ref "R43") (pin "2") (pinfunction "2_2") (pintype "passive"))
      (node (ref "S4") (pin "2") (pinfunction "S1_2") (pintype "passive"))
      (node (ref "TSOP4838") (pin "VCC") (pinfunction "V+_VCC") (pintype "bidirectional"))
      (node (ref "U$1") (pin "VCC") (pinfunction "VCC_VCC") (pintype "bidirectional"))
      (node (ref "U$1") (pin "VCC2") (pinfunction "VCC2_VCC2") (pintype "bidirectional"))
      (node (ref "U$1") (pin "VCC3") (pinfunction "VCC3_VCC3") (pintype "bidirectional"))
      (node (ref "U$10") (pin "2") (pinfunction "VO_2") (pintype "passive"))
      (node (ref "U$10") (pin "TAB") (pinfunction "OUT_TAB") (pintype "passive"))
      (node (ref "U$11") (pin "2") (pinfunction "VO_2") (pintype "passive"))
      (node (ref "U$11") (pin "TAB") (pinfunction "OUT_TAB") (pintype "passive"))
      (node (ref "U$12") (pin "+5V") (pinfunction "+5V_+5V") (pintype "bidirectional"))
      (node (ref "U$15") (pin "1") (pinfunction "VCC_1") (pintype "power_in"))
      (node (ref "U$17") (pin "LEGO") (pinfunction "LEGO_LEGO") (pintype "bidirectional"))
      (node (ref "U$2") (pin "+3V3") (pinfunction "+3V3_+3V3") (pintype "passive"))
      (node (ref "U$21") (pin "12") (pinfunction "VDDM_12") (pintype "bidirectional"))
      (node (ref "U$21") (pin "18") (pinfunction "VCC2_18") (pintype "bidirectional"))
      (node (ref "U$21") (pin "4") (pinfunction "VCC1_4") (pintype "bidirectional"))
      (node (ref "U$3") (pin "+5V") (pinfunction "+5V_+5V") (pintype "bidirectional"))
      (node (ref "U$3") (pin "5V") (pinfunction "5V_5V") (pintype "bidirectional"))
      (node (ref "U$4") (pin "+5V") (pinfunction "+5V_+5V") (pintype "bidirectional"))
      (node (ref "U$4") (pin "5V") (pinfunction "5V_5V") (pintype "bidirectional"))
      (node (ref "U3") (pin "VCC") (pinfunction "VCC_VCC") (pintype "bidirectional"))
      (node (ref "WS2812") (pin "1") (pinfunction "1_1") (pintype "passive"))
    )
    (net (code "2") (name "+5V") (class "Default")
      (node (ref "JP5") (pin "2") (pinfunction "2_2") (pintype "passive"))
      (node (ref "R33") (pin "1") (pinfunction "1_1") (pintype "passive"))
      (node (ref "R35") (pin "1") (pinfunction "1_1") (pintype "passive"))
      (node (ref "R37") (pin "1") (pinfunction "1_1") (pintype "passive"))
      (node (ref "R39") (pin "1") (pinfunction "1_1") (pintype "passive"))
      (node (ref "R44") (pin "1") (pinfunction "1_1") (pintype "passive"))
    )
    (net (code "3") (name "36") (class "Default")
      (node (ref "U$1") (pin "36") (pinfunction "36_36") (pintype "bidirectional"))
      (node (ref "U$2") (pin "+5V1") (pinfunction "+5V1_+5V1") (pintype "passive"))
    )
    (net (code "4") (name "A0") (class "Default")
      (node (ref "SW7") (pin "COM1") (pinfunction "COM1_COM1") (pintype "bidirectional"))
      (node (ref "U$1") (pin "A0") (pinfunction "A0_A0") (pintype "bidirectional"))
    )
    (net (code "5") (name "A0H") (class "Default")
      (node (ref "SW7") (pin "CH1B") (pinfunction "CH1B_CH1B") (pintype "bidirectional"))
      (node (ref "U$2") (pin "A0") (pinfunction "A0_A0") (pintype "passive"))
    )
    (net (code "6") (name "A1") (class "Default")
      (node (ref "POT") (pin "S") (pinfunction "S_S") (pintype "passive"))
      (node (ref "U$1") (pin "A1") (pinfunction "A1_A1") (pintype "bidirectional"))
      (node (ref "U$2") (pin "A1") (pinfunction "A1_A1") (pintype "passive"))
    )
    (net (code "7") (name "A2") (class "Default")
      (node (ref "R27") (pin "1") (pinfunction "1_1") (pintype "passive"))
      (node (ref "U$1") (pin "A2") (pinfunction "A2_A2") (pintype "bidirectional"))
    )
    (net (code "8") (name "A3") (class "Default")
      (node (ref "R28") (pin "2") (pinfunction "2_2") (pintype "passive"))
      (node (ref "U$1") (pin "A3") (pinfunction "A3_A3") (pintype "bidirectional"))
    )
    (net (code "9") (name "A6") (class "Default")
      (node (ref "SW4") (pin "COM1") (pinfunction "COM1_COM1") (pintype "bidirectional"))
      (node (ref "U$1") (pin "A6") (pinfunction "A6_A6") (pintype "bidirectional"))
    )
    (net (code "10") (name "A7") (class "Default")
      (node (ref "R21") (pin "2") (pinfunction "P$2_2") (pintype "bidirectional"))
      (node (ref "R32") (pin "1") (pinfunction "1_1") (pintype "passive"))
      (node (ref "U$1") (pin "A7") (pinfunction "A7_A7") (pintype "bidirectional"))
      (node (ref "U$2") (pin "A7") (pinfunction "A7_A7") (pintype "passive"))
    )
    (net (code "11") (name "ATMEGA_D+") (class "Default")
      (node (ref "SW1") (pin "CH2A") (pinfunction "CH2A_CH2A") (pintype "bidirectional"))
      (node (ref "U$1") (pin "D+") (pinfunction "D+_D+") (pintype "bidirectional"))
    )
    (net (code "12") (name "ATMEGA_D-") (class "Default")
      (node (ref "SW1") (pin "CH1A") (pinfunction "CH1A_CH1A") (pintype "bidirectional"))
      (node (ref "U$1") (pin "D-") (pinfunction "D-_D-") (pintype "bidirectional"))
    )
    (net (code "13") (name "BAT+") (class "Default")
      (node (ref "C15") (pin "1") (pinfunction "1_1") (pintype "passive"))
      (node (ref "L1") (pin "1") (pinfunction "1_1") (pintype "passive"))
      (node (ref "R41") (pin "1") (pinfunction "1_1") (pintype "passive"))
      (node (ref "R48") (pin "2") (pinfunction "2_2") (pintype "passive"))
      (node (ref "U$10") (pin "3") (pinfunction "VI_3") (pintype "input"))
      (node (ref "U$11") (pin "3") (pinfunction "VI_3") (pintype "input"))
      (node (ref "U$13") (pin "4") (pinfunction "AIN0_4") (pintype "input"))
      (node (ref "U$13") (pin "7") (pinfunction "AIN3_7") (pintype "input"))
      (node (ref "U$16") (pin "LEGO") (pinfunction "LEGO_LEGO") (pintype "bidirectional"))
      (node (ref "U$2") (pin "+5V") (pinfunction "+5V_+5V") (pintype "passive"))
      (node (ref "U$23") (pin "5") (pinfunction "+5V_5") (pintype "power_in"))
      (node (ref "U$5") (pin "P$4") (pinfunction "EN_P$4") (pintype "bidirectional"))
      (node (ref "U$5") (pin "P$5") (pinfunction "IN_P$5") (pintype "bidirectional"))
    )
    (net (code "14") (name "BAT-") (class "Default")
      (node (ref "1") (pin "2") (pinfunction "S_2") (pintype "passive"))
      (node (ref "1") (pin "3") (pinfunction "S_3") (pintype "passive"))
      (node (ref "8205") (pin "2") (pinfunction "S_2") (pintype "passive"))
      (node (ref "8205") (pin "3") (pinfunction "S_3") (pintype "passive"))
      (node (ref "BT1") (pin "GND@1") (pinfunction "-_GND@1") (pintype "power_in"))
      (node (ref "C16") (pin "2") (pinfunction "2_2") (pintype "passive"))
      (node (ref "ON") (pin "C") (pinfunction "C_C") (pintype "passive"))
      (node (ref "R6") (pin "1") (pinfunction "1_1") (pintype "passive"))
      (node (ref "U$7") (pin "-") (pinfunction "-_-") (pintype "power_in"))
      (node (ref "U$8") (pin "6") (pinfunction "GND_6") (pintype "bidirectional"))
    )
    (net (code "15") (name "BUTTON") (class "Default")
      (node (ref "R2") (pin "2") (pinfunction "2_2") (pintype "passive"))
      (node (ref "S4") (pin "4") (pinfunction "P1_4") (pintype "passive"))
      (node (ref "SW4") (pin "CH1B") (pinfunction "CH1B_CH1B") (pintype "bidirectional"))
    )
    (net (code "16") (name "CUR-SENSE") (class "Default")
      (node (ref "R22") (pin "1") (pinfunction "1_1") (pintype "passive"))
      (node (ref "R41") (pin "2") (pinfunction "2_2") (pintype "passive"))
      (node (ref "SW5") (pin "CH1B") (pinfunction "CH1B_CH1B") (pintype "bidirectional"))
      (node (ref "SW5") (pin "CH2B") (pinfunction "CH2B_CH2B") (pintype "bidirectional"))
      (node (ref "U$13") (pin "6") (pinfunction "AIN2_6") (pintype "input"))
    )
    (net (code "17") (name "D+") (class "Default")
      (node (ref "IC3") (pin "15") (pinfunction "USBDP_15") (pintype "bidirectional"))
      (node (ref "SW1") (pin "CH2B") (pinfunction "CH2B_CH2B") (pintype "bidirectional"))
    )
    (net (code "18") (name "D-") (class "Default")
      (node (ref "IC3") (pin "16") (pinfunction "USBDM_16") (pintype "bidirectional"))
      (node (ref "SW1") (pin "CH1B") (pinfunction "CH1B_CH1B") (pintype "bidirectional"))
    )
    (net (code "19") (name "D2") (class "Default")
      (node (ref "U$1") (pin "D2") (pinfunction "D2_D2") (pintype "bidirectional"))
      (node (ref "U$2") (pin "D2") (pinfunction "D2_D2") (pintype "passive"))
      (node (ref "U$23") (pin "3") (pinfunction "TX_3") (pintype "bidirectional"))
    )
    (net (code "20") (name "D3") (class "Default")
      (node (ref "U$1") (pin "D3") (pinfunction "D3_D3") (pintype "bidirectional"))
      (node (ref "U$2") (pin "D3") (pinfunction "D3_D3") (pintype "passive"))
    )
    (net (code "21") (name "D4") (class "Default")
      (node (ref "TSOP4838") (pin "OUT") (pinfunction "OUT_OUT") (pintype "bidirectional"))
      (node (ref "U$1") (pin "D4") (pinfunction "D4_D4") (pintype "bidirectional"))
      (node (ref "U$2") (pin "D4") (pinfunction "D4_D4") (pintype "passive"))
    )
    (net (code "22") (name "D5") (class "Default")
      (node (ref "U$1") (pin "D5") (pinfunction "D5_D5") (pintype "bidirectional"))
      (node (ref "U$2") (pin "D5") (pinfunction "D5_D5") (pintype "passive"))
      (node (ref "U$23") (pin "2") (pinfunction "RX_2") (pintype "bidirectional"))
    )
    (net (code "23") (name "D6") (class "Default")
      (node (ref "JP4") (pin "1") (pinfunction "1_1") (pintype "passive"))
      (node (ref "U$1") (pin "D6") (pinfunction "D6_D6") (pintype "bidirectional"))
      (node (ref "U$2") (pin "D6") (pinfunction "D6_D6") (pintype "passive"))
    )
    (net (code "24") (name "GND") (class "Default")
      (node (ref "1") (pin "6") (pinfunction "S_6") (pintype "passive"))
      (node (ref "1") (pin "7") (pinfunction "S_7") (pintype "passive"))
      (node (ref "8205") (pin "6") (pinfunction "S_6") (pintype "passive"))
      (node (ref "8205") (pin "7") (pinfunction "S_7") (pintype "passive"))
      (node (ref "C1") (pin "2") (pinfunction "2_2") (pintype "passive"))
      (node (ref "C10") (pin "2") (pinfunction "2_2") (pintype "passive"))
      (node (ref "C11") (pin "1") (pinfunction "1_1") (pintype "passive"))
      (node (ref "C12") (pin "2") (pinfunction "2_2") (pintype "passive"))
      (node (ref "C13") (pin "2") (pinfunction "2_2") (pintype "passive"))
      (node (ref "C14") (pin "2") (pinfunction "2_2") (pintype "passive"))
      (node (ref "C15") (pin "2") (pinfunction "2_2") (pintype "passive"))
      (node (ref "C17") (pin "-") (pinfunction "-_-") (pintype "passive"))
      (node (ref "C19") (pin "2") (pinfunction "2_2") (pintype "passive"))
      (node (ref "C2") (pin "2") (pinfunction "2_2") (pintype "passive"))
      (node (ref "C20") (pin "2") (pinfunction "2_2") (pintype "passive"))
      (node (ref "C5") (pin "2") (pinfunction "2_2") (pintype "passive"))
      (node (ref "C6") (pin "1") (pinfunction "1_1") (pintype "passive"))
      (node (ref "C7") (pin "1") (pinfunction "1_1") (pintype "passive"))
      (node (ref "C8") (pin "1") (pinfunction "1_1") (pintype "passive"))
      (node (ref "D1") (pin "A") (pinfunction "A_A") (pintype "passive"))
      (node (ref "IC1") (pin "12") (pinfunction "GND4_12") (pintype "power_in"))
      (node (ref "IC1") (pin "13") (pinfunction "GND3_13") (pintype "power_in"))
      (node (ref "IC1") (pin "4") (pinfunction "GND1_4") (pintype "power_in"))
      (node (ref "IC1") (pin "5") (pinfunction "GND2_5") (pintype "power_in"))
      (node (ref "IC2") (pin "3") (pinfunction "GND_3") (pintype "power_in"))
      (node (ref "IC3") (pin "18") (pinfunction "GND_18") (pintype "power_in"))
      (node (ref "IC3") (pin "21") (pinfunction "GND_21") (pintype "power_in"))
      (node (ref "IC3") (pin "25") (pinfunction "AGND_25") (pintype "power_in"))
      (node (ref "IC3") (pin "26") (pinfunction "TEST_26") (pintype "bidirectional"))
      (node (ref "IC3") (pin "7") (pinfunction "GND_7") (pintype "power_in"))
      (node (ref "IC5") (pin "1") (pinfunction "GND_1") (pintype "power_in"))
      (node (ref "IC5") (pin "5") (pinfunction "SDO_5") (pintype "input"))
      (node (ref "IC5") (pin "7") (pinfunction "GND_7") (pintype "power_in"))
      (node (ref "IRFU9024") (pin "G") (pinfunction "G_G") (pintype "passive"))
      (node (ref "JP2") (pin "3") (pinfunction "3_3") (pintype "passive"))
      (node (ref "JP3") (pin "3") (pinfunction "3_3") (pintype "passive"))
      (node (ref "JP4") (pin "3") (pinfunction "3_3") (pintype "passive"))
      (node (ref "JP5") (pin "6") (pinfunction "6_6") (pintype "passive"))
      (node (ref "LED10") (pin "4") (pinfunction "GND_4") (pintype "power_in"))
      (node (ref "LED11") (pin "4") (pinfunction "GND_4") (pintype "power_in"))
      (node (ref "LED4") (pin "4") (pinfunction "GND_4") (pintype "power_in"))
      (node (ref "LED5") (pin "3") (pinfunction "VSS_3") (pintype "bidirectional"))
      (node (ref "LED6") (pin "3") (pinfunction "VSS_3") (pintype "bidirectional"))
      (node (ref "LED7") (pin "3") (pinfunction "VSS_3") (pintype "bidirectional"))
      (node (ref "LED8") (pin "3") (pinfunction "VSS_3") (pintype "bidirectional"))
      (node (ref "LED9") (pin "4") (pinfunction "GND_4") (pintype "power_in"))
      (node (ref "LS1") (pin "E") (pinfunction "EMITTER_E") (pintype "passive"))
      (node (ref "LS1") (pin "K") (pinfunction "CATHODE_K") (pintype "passive"))
      (node (ref "LS2") (pin "E") (pinfunction "EMITTER_E") (pintype "passive"))
      (node (ref "LS2") (pin "K") (pinfunction "CATHODE_K") (pintype "passive"))
      (node (ref "POT") (pin "A") (pinfunction "A_A") (pintype "passive"))
      (node (ref "Q6") (pin "1") (pinfunction "G_1") (pintype "passive"))
      (node (ref "Q7") (pin "1") (pinfunction "G_1") (pintype "passive"))
      (node (ref "R12") (pin "2") (pinfunction "2_2") (pintype "passive"))
      (node (ref "R15") (pin "1") (pinfunction "1_1") (pintype "passive"))
      (node (ref "R2") (pin "1") (pinfunction "1_1") (pintype "passive"))
      (node (ref "R21") (pin "1") (pinfunction "P$1_1") (pintype "bidirectional"))
      (node (ref "R23") (pin "1") (pinfunction "P$1_1") (pintype "bidirectional"))
      (node (ref "R46") (pin "2") (pinfunction "2_2") (pintype "passive"))
      (node (ref "R47") (pin "2") (pinfunction "2_2") (pintype "passive"))
      (node (ref "R8") (pin "2") (pinfunction "2_2") (pintype "passive"))
      (node (ref "S2") (pin "4") (pinfunction "P1_4") (pintype "passive"))
      (node (ref "TP4056") (pin "1") (pinfunction "TEMP_1") (pintype "bidirectional"))
      (node (ref "TP4056") (pin "3") (pinfunction "GND_3") (pintype "bidirectional"))
      (node (ref "TSOP4838") (pin "GND") (pinfunction "GND_GND") (pintype "bidirectional"))
      (node (ref "U$1") (pin "GND") (pinfunction "GND_GND") (pintype "bidirectional"))
      (node (ref "U$1") (pin "GND2") (pinfunction "GND2_GND2") (pintype "bidirectional"))
      (node (ref "U$1") (pin "GND3") (pinfunction "GND3_GND3") (pintype "bidirectional"))
      (node (ref "U$10") (pin "1") (pinfunction "GND_1") (pintype "passive"))
      (node (ref "U$11") (pin "1") (pinfunction "GND_1") (pintype "passive"))
      (node (ref "U$12") (pin "GND") (pinfunction "GND_GND") (pintype "bidirectional"))
      (node (ref "U$13") (pin "1") (pinfunction "ADDR_1") (pintype "input"))
      (node (ref "U$13") (pin "3") (pinfunction "GND_3") (pintype "power_in"))
      (node (ref "U$13") (pin "5") (pinfunction "AIN1_5") (pintype "input"))
      (node (ref "U$14") (pin "2") (pinfunction "GND_2") (pintype "power_in"))
      (node (ref "U$15") (pin "2") (pinfunction "GND_2") (pintype "power_in"))
      (node (ref "U$18") (pin "LEGO") (pinfunction "LEGO_LEGO") (pintype "bidirectional"))
      (node (ref "U$19") (pin "LEGO") (pinfunction "LEGO_LEGO") (pintype "bidirectional"))
      (node (ref "U$2") (pin "GND") (pinfunction "GND_GND") (pintype "passive"))
      (node (ref "U$2") (pin "GND2") (pinfunction "GND1_GND2") (pintype "passive"))
      (node (ref "U$21") (pin "10") (pinfunction "ADDR1_10") (pintype "bidirectional"))
      (node (ref "U$21") (pin "17") (pinfunction "GND2_17") (pintype "bidirectional"))
      (node (ref "U$21") (pin "26") (pinfunction "ADDR0_26") (pintype "bidirectional"))
      (node (ref "U$21") (pin "3") (pinfunction "GND1_3") (pintype "bidirectional"))
      (node (ref "U$23") (pin "4") (pinfunction "GND_4") (pintype "power_in"))
      (node (ref "U$3") (pin "GND1") (pinfunction "GND_GND1") (pintype "bidirectional"))
      (node (ref "U$3") (pin "GND2") (pinfunction "GND2_GND2") (pintype "bidirectional"))
      (node (ref "U$4") (pin "GND") (pinfunction "GND_GND") (pintype "bidirectional"))
      (node (ref "U$4") (pin "GND2") (pinfunction "GND2_GND2") (pintype "bidirectional"))
      (node (ref "U$5") (pin "P$2") (pinfunction "GND_P$2") (pintype "bidirectional"))
      (node (ref "U$6") (pin "-") (pinfunction "-_-") (pintype "power_in"))
      (node (ref "U1") (pin "GND1") (pinfunction "GND_GND1") (pintype "bidirectional"))
      (node (ref "U3") (pin "GND") (pinfunction "GND_GND") (pintype "bidirectional"))
      (node (ref "WS2812") (pin "3") (pinfunction "3_3") (pintype "passive"))
    )
    (net (code "25") (name "HD_A6") (class "Default")
      (node (ref "SW4") (pin "CH1A") (pinfunction "CH1A_CH1A") (pintype "bidirectional"))
      (node (ref "U$2") (pin "A6") (pinfunction "A6_A6") (pintype "passive"))
    )
    (net (code "26") (name "IN_A1") (class "Default")
      (node (ref "IC1") (pin "2") (pinfunction "1A_2") (pintype "input"))
      (node (ref "JP3") (pin "1") (pinfunction "1_1") (pintype "passive"))
      (node (ref "R14") (pin "2") (pinfunction "2_2") (pintype "passive"))
      (node (ref "U$1") (pin "D10") (pinfunction "D10_D10") (pintype "bidirectional"))
    )
    (net (code "27") (name "IN_A2") (class "Default")
      (node (ref "IC1") (pin "7") (pinfunction "2A_7") (pintype "input"))
      (node (ref "JP2") (pin "1") (pinfunction "1_1") (pintype "passive"))
      (node (ref "R15") (pin "2") (pinfunction "2_2") (pintype "passive"))
      (node (ref "U$1") (pin "D9") (pinfunction "D9_D9") (pintype "bidirectional"))
    )
    (net (code "28") (name "IN_B1") (class "Default")
      (node (ref "IC1") (pin "15") (pinfunction "4A_15") (pintype "input"))
      (node (ref "R13") (pin "1") (pinfunction "1_1") (pintype "passive"))
      (node (ref "U$1") (pin "D8") (pinfunction "D8_D8") (pintype "bidirectional"))
    )
    (net (code "29") (name "IN_B2") (class "Default")
      (node (ref "IC1") (pin "10") (pinfunction "3A_10") (pintype "input"))
      (node (ref "R12") (pin "1") (pinfunction "1_1") (pintype "passive"))
      (node (ref "U$1") (pin "D7") (pinfunction "D7_D7") (pintype "bidirectional"))
    )
    (net (code "30") (name "IRFU") (class "Default")
      (node (ref "BT1") (pin "PWR@1") (pinfunction "+_PWR@1") (pintype "power_in"))
      (node (ref "C1") (pin "1") (pinfunction "1_1") (pintype "passive"))
      (node (ref "IRFU9024") (pin "D") (pinfunction "D_D") (pintype "passive"))
      (node (ref "Q6") (pin "2") (pinfunction "D_2") (pintype "passive"))
      (node (ref "Q7") (pin "2") (pinfunction "D_2") (pintype "passive"))
      (node (ref "REVERSE") (pin "C") (pinfunction "C_C") (pintype "passive"))
      (node (ref "SJ2") (pin "1") (pinfunction "1_1") (pintype "passive"))
      (node (ref "U$7") (pin "+") (pinfunction "+_+") (pintype "power_in"))
    )
    (net (code "31") (name "MISO") (class "Default")
      (node (ref "IC1") (pin "1") (pinfunction "1-2EN_1") (pintype "input"))
      (node (ref "Q4") (pin "2") (pinfunction "S_2") (pintype "passive"))
      (node (ref "R38") (pin "2") (pinfunction "2_2") (pintype "passive"))
      (node (ref "U$1") (pin "D12") (pinfunction "D12_D12") (pintype "bidirectional"))
    )
    (net (code "32") (name "MISO_HV") (class "Default")
      (node (ref "JP5") (pin "1") (pinfunction "1_1") (pintype "passive"))
      (node (ref "Q4") (pin "3") (pinfunction "D_3") (pintype "passive"))
      (node (ref "R37") (pin "2") (pinfunction "2_2") (pintype "passive"))
    )
    (net (code "33") (name "MOSI") (class "Default")
      (node (ref "IC1") (pin "9") (pinfunction "3-4EN_9") (pintype "input"))
      (node (ref "Q2") (pin "2") (pinfunction "S_2") (pintype "passive"))
      (node (ref "R34") (pin "2") (pinfunction "2_2") (pintype "passive"))
      (node (ref "U$1") (pin "D11") (pinfunction "D11_D11") (pintype "bidirectional"))
    )
    (net (code "34") (name "MOSI_HV") (class "Default")
      (node (ref "JP5") (pin "4") (pinfunction "4_4") (pintype "passive"))
      (node (ref "Q2") (pin "3") (pinfunction "D_3") (pintype "passive"))
      (node (ref "R33") (pin "2") (pinfunction "2_2") (pintype "passive"))
    )
    (net (code "35") (name "MOT_A+") (class "Default")
      (node (ref "IC1") (pin "3") (pinfunction "1Y_3") (pintype "output"))
      (node (ref "MOT_A") (pin "2") (pinfunction "KL_2") (pintype "passive"))
      (node (ref "U$24") (pin "+") (pinfunction "+_+") (pintype "bidirectional"))
    )
    (net (code "36") (name "MOT_A-") (class "Default")
      (node (ref "IC1") (pin "6") (pinfunction "2Y_6") (pintype "output"))
      (node (ref "MOT_A") (pin "1") (pinfunction "KL_1") (pintype "passive"))
      (node (ref "U$24") (pin "-") (pinfunction "-_-") (pintype "bidirectional"))
    )
    (net (code "37") (name "MOT_B+") (class "Default")
      (node (ref "IC1") (pin "14") (pinfunction "4Y_14") (pintype "output"))
      (node (ref "MOT_B") (pin "2") (pinfunction "KL_2") (pintype "passive"))
      (node (ref "U$9") (pin "+") (pinfunction "+_+") (pintype "bidirectional"))
    )
    (net (code "38") (name "MOT_B-") (class "Default")
      (node (ref "IC1") (pin "11") (pinfunction "3Y_11") (pintype "output"))
      (node (ref "MOT_B") (pin "1") (pinfunction "KL_1") (pintype "passive"))
      (node (ref "U$9") (pin "-") (pinfunction "-_-") (pintype "bidirectional"))
    )
    (net (code "39") (name "Net-(1A-D)") (class "Default")
      (node (ref "1") (pin "1") (pinfunction "D_1") (pintype "passive"))
      (node (ref "1") (pin "8") (pinfunction "D_8") (pintype "passive"))
    )
    (net (code "40") (name "Net-(1A-G)") (class "Default")
      (node (ref "1") (pin "4") (pinfunction "G_4") (pintype "passive"))
      (node (ref "8205") (pin "4") (pinfunction "G_4") (pintype "passive"))
      (node (ref "U$8") (pin "1") (pinfunction "0D_1") (pintype "bidirectional"))
    )
    (net (code "41") (name "Net-(1B-G)") (class "Default")
      (node (ref "1") (pin "5") (pinfunction "G_5") (pintype "passive"))
      (node (ref "8205") (pin "5") (pinfunction "G_5") (pintype "passive"))
      (node (ref "U$8") (pin "3") (pinfunction "0C_3") (pintype "bidirectional"))
    )
    (net (code "42") (name "Net-(8205A-D)") (class "Default")
      (node (ref "8205") (pin "1") (pinfunction "D_1") (pintype "passive"))
      (node (ref "8205") (pin "8") (pinfunction "D_8") (pintype "passive"))
    )
    (net (code "43") (name "Net-(C7-Pad2)") (class "Default")
      (node (ref "C7") (pin "2") (pinfunction "2_2") (pintype "passive"))
      (node (ref "Q1") (pin "1") (pinfunction "1_1") (pintype "passive"))
      (node (ref "U$1") (pin "CRYST1") (pinfunction "CRYST1_CRYST1") (pintype "bidirectional"))
    )
    (net (code "44") (name "Net-(C8-Pad2)") (class "Default")
      (node (ref "C8") (pin "2") (pinfunction "2_2") (pintype "passive"))
      (node (ref "Q1") (pin "3") (pinfunction "3_3") (pintype "passive"))
      (node (ref "U$1") (pin "CRYST2") (pinfunction "CRYST2_CRYST2") (pintype "bidirectional"))
    )
    (net (code "45") (name "Net-(C14-Pad1)") (class "Default")
      (node (ref "C14") (pin "1") (pinfunction "1_1") (pintype "passive"))
      (node (ref "D3") (pin "C") (pinfunction "C_C") (pintype "passive"))
      (node (ref "R49") (pin "1") (pinfunction "1_1") (pintype "passive"))
      (node (ref "R9") (pin "1") (pinfunction "1_1") (pintype "passive"))
      (node (ref "SJ1") (pin "1") (pinfunction "1_1") (pintype "passive"))
    )
    (net (code "46") (name "Net-(IC1-VCC2)") (class "Default")
      (node (ref "IC1") (pin "8") (pinfunction "VCC2_8") (pintype "power_in"))
      (node (ref "SW6") (pin "CH1A") (pinfunction "CH1A_CH1A") (pintype "bidirectional"))
      (node (ref "SW6") (pin "CH2A") (pinfunction "CH2A_CH2A") (pintype "bidirectional"))
    )
    (net (code "47") (name "Net-(IC2-OUT)") (class "Default")
      (node (ref "D1") (pin "C") (pinfunction "C_C") (pintype "passive"))
      (node (ref "IC2") (pin "2") (pinfunction "OUT_2") (pintype "output"))
      (node (ref "L2") (pin "1") (pinfunction "1_1") (pintype "passive"))
    )
    (net (code "48") (name "Net-(IC3-3V3OUT)") (class "Default")
      (node (ref "C2") (pin "1") (pinfunction "1_1") (pintype "passive"))
      (node (ref "IC3") (pin "17") (pinfunction "3V3OUT_17") (pintype "output"))
      (node (ref "IC3") (pin "4") (pinfunction "VCCIO_4") (pintype "power_in"))
      (node (ref "R24") (pin "1") (pinfunction "1_1") (pintype "passive"))
      (node (ref "R25") (pin "1") (pinfunction "1_1") (pintype "passive"))
    )
    (net (code "49") (name "Net-(IC3-CBUS0)") (class "Default")
      (node (ref "IC3") (pin "23") (pinfunction "CBUS0_23") (pintype "bidirectional"))
      (node (ref "TXD") (pin "C") (pinfunction "C_C") (pintype "passive"))
    )
    (net (code "50") (name "Net-(IC3-CBUS1)") (class "Default")
      (node (ref "IC3") (pin "22") (pinfunction "CBUS1_22") (pintype "bidirectional"))
      (node (ref "LED3") (pin "C") (pinfunction "C_C") (pintype "passive"))
    )
    (net (code "51") (name "Net-(IC3-_DTR)") (class "Default")
      (node (ref "C3") (pin "1") (pinfunction "1_1") (pintype "passive"))
      (node (ref "IC3") (pin "2") (pinfunction "_DTR_2") (pintype "input"))
    )
    (net (code "52") (name "Net-(IC3-_RTS)") (class "Default")
      (node (ref "C18") (pin "2") (pinfunction "2_2") (pintype "passive"))
      (node (ref "IC3") (pin "3") (pinfunction "_RTS_3") (pintype "output"))
    )
    (net (code "53") (name "Net-(LED1-PadC)") (class "Default")
      (node (ref "LED1") (pin "C") (pinfunction "C_C") (pintype "passive"))
      (node (ref "R5") (pin "1") (pinfunction "1_1") (pintype "passive"))
    )
    (net (code "54") (name "Net-(LED3-PadA)") (class "Default")
      (node (ref "LED3") (pin "A") (pinfunction "A_A") (pintype "passive"))
      (node (ref "R24") (pin "2") (pinfunction "2_2") (pintype "passive"))
    )
    (net (code "55") (name "Net-(LED4-DI)") (class "Default")
      (node (ref "LED4") (pin "1") (pinfunction "DI_1") (pintype "input"))
      (node (ref "LED6") (pin "2") (pinfunction "DO_2") (pintype "bidirectional"))
      (node (ref "LED7") (pin "4") (pinfunction "DI_4") (pintype "bidirectional"))
      (node (ref "LED9") (pin "3") (pinfunction "DO_3") (pintype "output"))
    )
    (net (code "56") (name "Net-(LED10-DI)") (class "Default")
      (node (ref "LED10") (pin "1") (pinfunction "DI_1") (pintype "input"))
      (node (ref "LED5") (pin "4") (pinfunction "DI_4") (pintype "bidirectional"))
      (node (ref "R7") (pin "1") (pinfunction "1_1") (pintype "passive"))
    )
    (net (code "57") (name "Net-(LED10-DO)") (class "Default")
      (node (ref "LED10") (pin "3") (pinfunction "DO_3") (pintype "output"))
      (node (ref "LED5") (pin "2") (pinfunction "DO_2") (pintype "bidirectional"))
      (node (ref "LED6") (pin "4") (pinfunction "DI_4") (pintype "bidirectional"))
      (node (ref "LED9") (pin "1") (pinfunction "DI_1") (pintype "input"))
    )
    (net (code "58") (name "Net-(LED11-DI)") (class "Default")
      (node (ref "LED11") (pin "1") (pinfunction "DI_1") (pintype "input"))
      (node (ref "LED4") (pin "3") (pinfunction "DO_3") (pintype "output"))
      (node (ref "LED7") (pin "2") (pinfunction "DO_2") (pintype "bidirectional"))
      (node (ref "LED8") (pin "4") (pinfunction "DI_4") (pintype "bidirectional"))
    )
    (net (code "59") (name "Net-(LED11-DO)") (class "Default")
      (node (ref "LED11") (pin "3") (pinfunction "DO_3") (pintype "output"))
      (node (ref "LED8") (pin "2") (pinfunction "DO_2") (pintype "bidirectional"))
      (node (ref "WS2812") (pin "2") (pinfunction "2_2") (pintype "passive"))
    )
    (net (code "60") (name "Net-(LS1-ANODE)") (class "Default")
      (node (ref "LS1") (pin "A") (pinfunction "ANODE_A") (pintype "passive"))
      (node (ref "R18") (pin "2") (pinfunction "2_2") (pintype "passive"))
    )
    (net (code "61") (name "Net-(LS1-COLLECTOR)") (class "Default")
      (node (ref "LS1") (pin "C") (pinfunction "COLLECTOR_C") (pintype "passive"))
      (node (ref "R19") (pin "2") (pinfunction "2_2") (pintype "passive"))
      (node (ref "SW3") (pin "CH1B") (pinfunction "CH1B_CH1B") (pintype "bidirectional"))
      (node (ref "TXD1") (pin "C") (pinfunction "C_C") (pintype "passive"))
    )
    (net (code "62") (name "Net-(LS2-ANODE)") (class "Default")
      (node (ref "LS2") (pin "A") (pinfunction "ANODE_A") (pintype "passive"))
      (node (ref "R16") (pin "2") (pinfunction "2_2") (pintype "passive"))
    )
    (net (code "63") (name "Net-(LS2-COLLECTOR)") (class "Default")
      (node (ref "LS2") (pin "C") (pinfunction "COLLECTOR_C") (pintype "passive"))
      (node (ref "R17") (pin "2") (pinfunction "2_2") (pintype "passive"))
      (node (ref "SW2") (pin "CH1A") (pinfunction "CH1A_CH1A") (pintype "bidirectional"))
      (node (ref "TXD2") (pin "C") (pinfunction "C_C") (pintype "passive"))
    )
    (net (code "64") (name "Net-(ON-PadA)") (class "Default")
      (node (ref "ON") (pin "A") (pinfunction "A_A") (pintype "passive"))
      (node (ref "R22") (pin "2") (pinfunction "2_2") (pintype "passive"))
    )
    (net (code "65") (name "Net-(Q6-S)") (class "Default")
      (node (ref "IRFU9024") (pin "S") (pinfunction "S_S") (pintype "passive"))
      (node (ref "Q6") (pin "3") (pinfunction "S_3") (pintype "passive"))
      (node (ref "Q7") (pin "3") (pinfunction "S_3") (pintype "passive"))
      (node (ref "SJ2") (pin "2") (pinfunction "2_2") (pintype "passive"))
      (node (ref "SW5") (pin "COM1") (pinfunction "COM1_COM1") (pintype "bidirectional"))
      (node (ref "SW5") (pin "COM2") (pinfunction "COM2_COM2") (pintype "bidirectional"))
      (node (ref "TP4056") (pin "5") (pinfunction "BAT_5") (pintype "bidirectional"))
    )
    (net (code "66") (name "Net-(R4-Pad2)") (class "Default")
      (node (ref "R4") (pin "2") (pinfunction "2_2") (pintype "passive"))
      (node (ref "R8") (pin "1") (pinfunction "1_1") (pintype "passive"))
    )
    (net (code "67") (name "Net-(R6-Pad2)") (class "Default")
      (node (ref "R6") (pin "2") (pinfunction "2_2") (pintype "passive"))
      (node (ref "REVERSE") (pin "A") (pinfunction "A_A") (pintype "passive"))
    )
    (net (code "68") (name "Net-(R10-Pad1)") (class "Default")
      (node (ref "R10") (pin "1") (pinfunction "1_1") (pintype "passive"))
      (node (ref "TXD1") (pin "A") (pinfunction "A_A") (pintype "passive"))
    )
    (net (code "69") (name "Net-(R11-Pad1)") (class "Default")
      (node (ref "R11") (pin "1") (pinfunction "1_1") (pintype "passive"))
      (node (ref "YELLOW") (pin "C") (pinfunction "C_C") (pintype "passive"))
    )
    (net (code "70") (name "Net-(R20-Pad1)") (class "Default")
      (node (ref "R20") (pin "1") (pinfunction "1_1") (pintype "passive"))
      (node (ref "TXD2") (pin "A") (pinfunction "A_A") (pintype "passive"))
    )
    (net (code "71") (name "Net-(R23-P$2)") (class "Default")
      (node (ref "R23") (pin "2") (pinfunction "P$2_2") (pintype "bidirectional"))
      (node (ref "R29") (pin "1") (pinfunction "1_1") (pintype "passive"))
      (node (ref "SW7") (pin "CH1A") (pinfunction "CH1A_CH1A") (pintype "bidirectional"))
    )
    (net (code "72") (name "Net-(R25-Pad2)") (class "Default")
      (node (ref "R25") (pin "2") (pinfunction "2_2") (pintype "passive"))
      (node (ref "TXD") (pin "A") (pinfunction "A_A") (pintype "passive"))
    )
    (net (code "73") (name "Net-(R26-Pad2)") (class "Default")
      (node (ref "R26") (pin "2") (pinfunction "2_2") (pintype "passive"))
      (node (ref "U$12") (pin "A1") (pinfunction "A1_A1") (pintype "bidirectional"))
    )
    (net (code "74") (name "Net-(R27-Pad2)") (class "Default")
      (node (ref "R27") (pin "2") (pinfunction "2_2") (pintype "passive"))
      (node (ref "SW3") (pin "COM1") (pinfunction "COM1_COM1") (pintype "bidirectional"))
    )
    (net (code "75") (name "Net-(R28-Pad1)") (class "Default")
      (node (ref "R28") (pin "1") (pinfunction "1_1") (pintype "passive"))
      (node (ref "SW2") (pin "COM1") (pinfunction "COM1_COM1") (pintype "bidirectional"))
    )
    (net (code "76") (name "Net-(SW2-PadCH1B)") (class "Default")
      (node (ref "SW2") (pin "CH1B") (pinfunction "CH1B_CH1B") (pintype "bidirectional"))
      (node (ref "U$12") (pin "A3") (pinfunction "A3_A3") (pintype "bidirectional"))
    )
    (net (code "77") (name "Net-(SW3-PadCH1A)") (class "Default")
      (node (ref "SW3") (pin "CH1A") (pinfunction "CH1A_CH1A") (pintype "bidirectional"))
      (node (ref "U$12") (pin "A2") (pinfunction "A2_A2") (pintype "bidirectional"))
    )
    (net (code "78") (name "Net-(TP4056-CE)") (class "Default")
      (node (ref "LED1") (pin "A") (pinfunction "A_A") (pintype "passive"))
      (node (ref "R3") (pin "2") (pinfunction "2_2") (pintype "passive"))
      (node (ref "TP4056") (pin "4") (pinfunction "VCC_4") (pintype "bidirectional"))
      (node (ref "TP4056") (pin "8") (pinfunction "CE_8") (pintype "bidirectional"))
      (node (ref "YELLOW") (pin "A") (pinfunction "A_A") (pintype "passive"))
    )
    (net (code "79") (name "Net-(TP4056-CHRG)") (class "Default")
      (node (ref "R5") (pin "2") (pinfunction "2_2") (pintype "passive"))
      (node (ref "TP4056") (pin "7") (pinfunction "CHRG_7") (pintype "bidirectional"))
    )
    (net (code "80") (name "Net-(TP4056-PROG)") (class "Default")
      (node (ref "R4") (pin "1") (pinfunction "1_1") (pintype "passive"))
      (node (ref "TP4056") (pin "2") (pinfunction "PROG_2") (pintype "bidirectional"))
    )
    (net (code "81") (name "Net-(TP4056-STDBY)") (class "Default")
      (node (ref "R11") (pin "2") (pinfunction "2_2") (pintype "passive"))
      (node (ref "TP4056") (pin "6") (pinfunction "STDBY_6") (pintype "bidirectional"))
    )
    (net (code "82") (name "Net-(U$5-FB)") (class "Default")
      (node (ref "R46") (pin "1") (pinfunction "1_1") (pintype "passive"))
      (node (ref "R49") (pin "2") (pinfunction "2_2") (pintype "passive"))
      (node (ref "R9") (pin "2") (pinfunction "2_2") (pintype "passive"))
      (node (ref "U$5") (pin "P$3") (pinfunction "FB_P$3") (pintype "bidirectional"))
    )
    (net (code "83") (name "Net-(U$5-SW)") (class "Default")
      (node (ref "D3") (pin "A") (pinfunction "A_A") (pintype "passive"))
      (node (ref "L1") (pin "2") (pinfunction "2_2") (pintype "passive"))
      (node (ref "U$5") (pin "P$1") (pinfunction "SW_P$1") (pintype "bidirectional"))
    )
    (net (code "84") (name "Net-(U$8-CS)") (class "Default")
      (node (ref "R47") (pin "1") (pinfunction "1_1") (pintype "passive"))
      (node (ref "U$8") (pin "2") (pinfunction "CS_2") (pintype "bidirectional"))
    )
    (net (code "85") (name "Net-(U$8-VCC)") (class "Default")
      (node (ref "C16") (pin "1") (pinfunction "1_1") (pintype "passive"))
      (node (ref "R48") (pin "1") (pinfunction "1_1") (pintype "passive"))
      (node (ref "U$8") (pin "5") (pinfunction "VCC_5") (pintype "bidirectional"))
    )
    (net (code "86") (name "Net-(U$21-I{slash}O[0])") (class "Default")
      (node (ref "JP11") (pin "1") (pinfunction "1_1") (pintype "passive"))
      (node (ref "U$21") (pin "27") (pinfunction "I/O[0]_27") (pintype "bidirectional"))
    )
    (net (code "87") (name "Net-(U$21-I{slash}O[1])") (class "Default")
      (node (ref "JP10") (pin "1") (pinfunction "1_1") (pintype "passive"))
      (node (ref "U$21") (pin "28") (pinfunction "I/O[1]_28") (pintype "bidirectional"))
    )
    (net (code "88") (name "Net-(U$21-I{slash}O[2])") (class "Default")
      (node (ref "JP8") (pin "1") (pinfunction "1_1") (pintype "passive"))
      (node (ref "U$21") (pin "1") (pinfunction "I/O[2]_1") (pintype "bidirectional"))
    )
    (net (code "89") (name "Net-(U$21-I{slash}O[3])") (class "Default")
      (node (ref "JP9") (pin "1") (pinfunction "1_1") (pintype "passive"))
      (node (ref "U$21") (pin "2") (pinfunction "I/O[3]_2") (pintype "bidirectional"))
    )
    (net (code "90") (name "Net-(U$21-I{slash}O[4])") (class "Default")
      (node (ref "JP7") (pin "1") (pinfunction "1_1") (pintype "passive"))
      (node (ref "U$21") (pin "5") (pinfunction "I/O[4]_5") (pintype "bidirectional"))
    )
    (net (code "91") (name "Net-(U$21-I{slash}O[5])") (class "Default")
      (node (ref "JP6") (pin "1") (pinfunction "1_1") (pintype "passive"))
      (node (ref "U$21") (pin "6") (pinfunction "I/O[5]_6") (pintype "bidirectional"))
    )
    (net (code "92") (name "Net-(U$21-I{slash}O[6])") (class "Default")
      (node (ref "JP1") (pin "1") (pinfunction "1_1") (pintype "passive"))
      (node (ref "U$21") (pin "7") (pinfunction "I/O[6]_7") (pintype "bidirectional"))
    )
    (net (code "93") (name "Net-(U$21-I{slash}O[7])") (class "Default")
      (node (ref "JP18") (pin "1") (pinfunction "1_1") (pintype "passive"))
      (node (ref "U$21") (pin "8") (pinfunction "I/O[7]_8") (pintype "bidirectional"))
    )
    (net (code "94") (name "Net-(U$21-I{slash}O[8])") (class "Default")
      (node (ref "JP17") (pin "1") (pinfunction "1_1") (pintype "passive"))
      (node (ref "U$21") (pin "13") (pinfunction "I/O[8]_13") (pintype "bidirectional"))
    )
    (net (code "95") (name "Net-(U$21-I{slash}O[9])") (class "Default")
      (node (ref "JP16") (pin "1") (pinfunction "1_1") (pintype "passive"))
      (node (ref "U$21") (pin "14") (pinfunction "I/O[9]_14") (pintype "bidirectional"))
    )
    (net (code "96") (name "Net-(U$21-I{slash}O[10])") (class "Default")
      (node (ref "JP15") (pin "1") (pinfunction "1_1") (pintype "passive"))
      (node (ref "U$21") (pin "15") (pinfunction "I/O[10]_15") (pintype "bidirectional"))
    )
    (net (code "97") (name "Net-(U$21-I{slash}O[11])") (class "Default")
      (node (ref "JP19") (pin "1") (pinfunction "1_1") (pintype "passive"))
      (node (ref "U$21") (pin "16") (pinfunction "I/O[11]_16") (pintype "bidirectional"))
    )
    (net (code "98") (name "Net-(U$21-I{slash}O[12])") (class "Default")
      (node (ref "JP14") (pin "1") (pinfunction "1_1") (pintype "passive"))
      (node (ref "U$21") (pin "19") (pinfunction "I/O[12]_19") (pintype "bidirectional"))
    )
    (net (code "99") (name "Net-(U$21-I{slash}O[13])") (class "Default")
      (node (ref "JP13") (pin "1") (pinfunction "1_1") (pintype "passive"))
      (node (ref "U$21") (pin "20") (pinfunction "I/O[13]_20") (pintype "bidirectional"))
    )
    (net (code "100") (name "Net-(U$21-I{slash}O[14])") (class "Default")
      (node (ref "JP12") (pin "1") (pinfunction "1_1") (pintype "passive"))
      (node (ref "U$21") (pin "21") (pinfunction "I/O[14]_21") (pintype "bidirectional"))
    )
    (net (code "101") (name "Net-(U$21-I{slash}O[15])") (class "Default")
      (node (ref "JP20") (pin "1") (pinfunction "1_1") (pintype "passive"))
      (node (ref "U$21") (pin "22") (pinfunction "I/O[15]_22") (pintype "bidirectional"))
    )
    (net (code "102") (name "Net-(U$21-NINT)") (class "Default")
      (node (ref "R42") (pin "2") (pinfunction "2_2") (pintype "passive"))
      (node (ref "U$21") (pin "9") (pinfunction "NINT_9") (pintype "bidirectional"))
    )
    (net (code "103") (name "Net-(U$21-NRESET)") (class "Default")
      (node (ref "R43") (pin "1") (pinfunction "1_1") (pintype "passive"))
      (node (ref "U$21") (pin "23") (pinfunction "NRESET_23") (pintype "bidirectional"))
    )
    (net (code "104") (name "Net-(U1-D+)") (class "Default")
      (node (ref "SW1") (pin "COM2") (pinfunction "COM2_COM2") (pintype "bidirectional"))
      (node (ref "U1") (pin "D+1") (pinfunction "D+_D+1") (pintype "bidirectional"))
    )
    (net (code "105") (name "Net-(U1-D-)") (class "Default")
      (node (ref "SW1") (pin "COM1") (pinfunction "COM1_COM1") (pintype "bidirectional"))
      (node (ref "U1") (pin "D-1") (pinfunction "D-_D-1") (pintype "bidirectional"))
    )
    (net (code "106") (name "RESET") (class "Default")
      (node (ref "C18") (pin "1") (pinfunction "1_1") (pintype "passive"))
      (node (ref "C3") (pin "2") (pinfunction "2_2") (pintype "passive"))
      (node (ref "Q3") (pin "2") (pinfunction "S_2") (pintype "passive"))
      (node (ref "R1") (pin "1") (pinfunction "1_1") (pintype "passive"))
      (node (ref "S2") (pin "2") (pinfunction "S1_2") (pintype "passive"))
      (node (ref "U$1") (pin "RESET") (pinfunction "RESET_RESET") (pintype "bidirectional"))
    )
    (net (code "107") (name "RESET_HV") (class "Default")
      (node (ref "JP5") (pin "5") (pinfunction "5_5") (pintype "passive"))
      (node (ref "Q3") (pin "3") (pinfunction "D_3") (pintype "passive"))
      (node (ref "R35") (pin "2") (pinfunction "2_2") (pintype "passive"))
    )
    (net (code "108") (name "RXD") (class "Default")
      (node (ref "IC3") (pin "1") (pinfunction "TXD_1") (pintype "output"))
      (node (ref "U$1") (pin "D0") (pinfunction "D0_D0") (pintype "bidirectional"))
      (node (ref "U$2") (pin "D0") (pinfunction "D0_D0") (pintype "passive"))
      (node (ref "U$4") (pin "RXD") (pinfunction "RXD1_RXD") (pintype "bidirectional"))
      (node (ref "U$4") (pin "RXD2") (pinfunction "RXD2_RXD2") (pintype "bidirectional"))
    )
    (net (code "109") (name "SCK") (class "Default")
      (node (ref "Q5") (pin "2") (pinfunction "S_2") (pintype "passive"))
      (node (ref "R26") (pin "1") (pinfunction "1_1") (pintype "passive"))
      (node (ref "R40") (pin "2") (pinfunction "2_2") (pintype "passive"))
      (node (ref "R7") (pin "2") (pinfunction "2_2") (pintype "passive"))
      (node (ref "U$1") (pin "D13") (pinfunction "D13_D13") (pintype "bidirectional"))
    )
    (net (code "110") (name "SCK_HV") (class "Default")
      (node (ref "JP5") (pin "3") (pinfunction "3_3") (pintype "passive"))
      (node (ref "Q5") (pin "3") (pinfunction "D_3") (pintype "passive"))
      (node (ref "R39") (pin "2") (pinfunction "2_2") (pintype "passive"))
    )
    (net (code "111") (name "SCL") (class "Default")
      (node (ref "IC5") (pin "4") (pinfunction "SCK_4") (pintype "bidirectional"))
      (node (ref "JP23") (pin "2") (pinfunction "2_2") (pintype "passive"))
      (node (ref "R30") (pin "1") (pinfunction "1_1") (pintype "passive"))
      (node (ref "U$1") (pin "A5") (pinfunction "A5_A5") (pintype "bidirectional"))
      (node (ref "U$13") (pin "10") (pinfunction "SCL_10") (pintype "bidirectional"))
      (node (ref "U$14") (pin "3") (pinfunction "SCL_3") (pintype "bidirectional"))
      (node (ref "U$15") (pin "3") (pinfunction "SCL_3") (pintype "bidirectional"))
      (node (ref "U$2") (pin "A5") (pinfunction "A5_A5") (pintype "passive"))
      (node (ref "U$21") (pin "25") (pinfunction "SCL_25") (pintype "bidirectional"))
      (node (ref "U$3") (pin "SCL") (pinfunction "SCL_SCL") (pintype "bidirectional"))
      (node (ref "U$3") (pin "SCL2") (pinfunction "SCL2_SCL2") (pintype "bidirectional"))
      (node (ref "U3") (pin "SCL") (pinfunction "SCL_SCL") (pintype "bidirectional"))
    )
    (net (code "112") (name "SDA") (class "Default")
      (node (ref "IC5") (pin "3") (pinfunction "SDI_3") (pintype "bidirectional"))
      (node (ref "JP23") (pin "1") (pinfunction "1_1") (pintype "passive"))
      (node (ref "R31") (pin "1") (pinfunction "1_1") (pintype "passive"))
      (node (ref "U$1") (pin "A4") (pinfunction "A4_A4") (pintype "bidirectional"))
      (node (ref "U$13") (pin "9") (pinfunction "SDA_9") (pintype "bidirectional"))
      (node (ref "U$14") (pin "4") (pinfunction "SDA_4") (pintype "bidirectional"))
      (node (ref "U$15") (pin "4") (pinfunction "SDA_4") (pintype "bidirectional"))
      (node (ref "U$2") (pin "A4") (pinfunction "A4_A4") (pintype "passive"))
      (node (ref "U$21") (pin "24") (pinfunction "SDA_24") (pintype "bidirectional"))
      (node (ref "U$3") (pin "SDA") (pinfunction "SDA_SDA") (pintype "bidirectional"))
      (node (ref "U$3") (pin "SDA2") (pinfunction "SDA2_SDA2") (pintype "bidirectional"))
      (node (ref "U3") (pin "SDA") (pinfunction "SDA_SDA") (pintype "bidirectional"))
    )
    (net (code "113") (name "TXD") (class "Default")
      (node (ref "IC3") (pin "5") (pinfunction "RXD_5") (pintype "input"))
      (node (ref "U$1") (pin "D1") (pinfunction "D1_D1") (pintype "bidirectional"))
      (node (ref "U$2") (pin "D1") (pinfunction "D1_D1") (pintype "passive"))
      (node (ref "U$4") (pin "TXD") (pinfunction "TXD_TXD") (pintype "bidirectional"))
      (node (ref "U$4") (pin "TXD2") (pinfunction "TXD2_TXD2") (pintype "bidirectional"))
    )
    (net (code "114") (name "VCC_MOT") (class "Default")
      (node (ref "IC2") (pin "1") (pinfunction "VIN_1") (pintype "power_in"))
      (node (ref "SJ1") (pin "2") (pinfunction "2_2") (pintype "passive"))
      (node (ref "SW6") (pin "COM1") (pinfunction "COM1_COM1") (pintype "bidirectional"))
      (node (ref "SW6") (pin "COM2") (pinfunction "COM2_COM2") (pintype "bidirectional"))
      (node (ref "U$6") (pin "+") (pinfunction "+_+") (pintype "power_in"))
    )
    (net (code "115") (name "VCC_SERVO") (class "Default")
      (node (ref "C17") (pin "+") (pinfunction "+_+") (pintype "passive"))
      (node (ref "IC2") (pin "4") (pinfunction "FB_4") (pintype "input"))
      (node (ref "JP2") (pin "2") (pinfunction "2_2") (pintype "passive"))
      (node (ref "JP3") (pin "2") (pinfunction "2_2") (pintype "passive"))
      (node (ref "JP4") (pin "2") (pinfunction "2_2") (pintype "passive"))
      (node (ref "L2") (pin "2") (pinfunction "2_2") (pintype "passive"))
      (node (ref "R44") (pin "2") (pinfunction "2_2") (pintype "passive"))
      (node (ref "U$13") (pin "8") (pinfunction "VDD_8") (pintype "power_in"))
      (node (ref "U$14") (pin "1") (pinfunction "VIN_1") (pintype "power_in"))
    )
    (net (code "116") (name "VUSB") (class "Default")
      (node (ref "IC3") (pin "20") (pinfunction "VCC_20") (pintype "power_in"))
      (node (ref "R3") (pin "1") (pinfunction "1_1") (pintype "passive"))
      (node (ref "U1") (pin "VBUS1") (pinfunction "VBUS_VBUS1") (pintype "bidirectional"))
    )
    (net (code "117") (name "unconnected-(IC2-OFF-Pad5)") (class "Default")
      (node (ref "IC2") (pin "5") (pinfunction "OFF_5") (pintype "input"))
    )
    (net (code "118") (name "unconnected-(IC3-CBUS2-Pad13)") (class "Default")
      (node (ref "IC3") (pin "13") (pinfunction "CBUS2_13") (pintype "bidirectional"))
    )
    (net (code "119") (name "unconnected-(IC3-CBUS3-Pad14)") (class "Default")
      (node (ref "IC3") (pin "14") (pinfunction "CBUS3_14") (pintype "bidirectional"))
    )
    (net (code "120") (name "unconnected-(IC3-CBUS4-Pad12)") (class "Default")
      (node (ref "IC3") (pin "12") (pinfunction "CBUS4_12") (pintype "bidirectional"))
    )
    (net (code "121") (name "unconnected-(IC3-NC-Pad8)") (class "Default")
      (node (ref "IC3") (pin "8") (pinfunction "NC_8") (pintype "no_connect"))
    )
    (net (code "122") (name "unconnected-(IC3-NC-Pad24)") (class "Default")
      (node (ref "IC3") (pin "24") (pinfunction "NC_24") (pintype "no_connect"))
    )
    (net (code "123") (name "unconnected-(IC3-OSCI-Pad27)") (class "Default")
      (node (ref "IC3") (pin "27") (pinfunction "OSCI_27") (pintype "input"))
    )
    (net (code "124") (name "unconnected-(IC3-OSCO-Pad28)") (class "Default")
      (node (ref "IC3") (pin "28") (pinfunction "OSCO_28") (pintype "output"))
    )
    (net (code "125") (name "unconnected-(IC3-_CTS-Pad11)") (class "Default")
      (node (ref "IC3") (pin "11") (pinfunction "_CTS_11") (pintype "input"))
    )
    (net (code "126") (name "unconnected-(IC3-_DCD-Pad10)") (class "Default")
      (node (ref "IC3") (pin "10") (pinfunction "_DCD_10") (pintype "input"))
    )
    (net (code "127") (name "unconnected-(IC3-_DSR-Pad9)") (class "Default")
      (node (ref "IC3") (pin "9") (pinfunction "_DSR_9") (pintype "input"))
    )
    (net (code "128") (name "unconnected-(IC3-_RESET-Pad19)") (class "Default")
      (node (ref "IC3") (pin "19") (pinfunction "_RESET_19") (pintype "input"))
    )
    (net (code "129") (name "unconnected-(IC3-_RI-Pad6)") (class "Default")
      (node (ref "IC3") (pin "6") (pinfunction "_RI_6") (pintype "input"))
    )
    (net (code "130") (name "unconnected-(Q1-Pad2)") (class "Default")
      (node (ref "Q1") (pin "2") (pinfunction "2_2") (pintype "passive"))
    )
    (net (code "131") (name "unconnected-(S2-P-Pad3)") (class "Default")
      (node (ref "S2") (pin "3") (pinfunction "P_3") (pintype "passive"))
    )
    (net (code "132") (name "unconnected-(S2-S-Pad1)") (class "Default")
      (node (ref "S2") (pin "1") (pinfunction "S_1") (pintype "passive"))
    )
    (net (code "133") (name "unconnected-(S4-P-Pad3)") (class "Default")
      (node (ref "S4") (pin "3") (pinfunction "P_3") (pintype "passive"))
    )
    (net (code "134") (name "unconnected-(S4-S-Pad1)") (class "Default")
      (node (ref "S4") (pin "1") (pinfunction "S_1") (pintype "passive"))
    )
    (net (code "135") (name "unconnected-(SW2-PadCH2A)") (class "Default")
      (node (ref "SW2") (pin "CH2A") (pinfunction "CH2A_CH2A") (pintype "bidirectional"))
    )
    (net (code "136") (name "unconnected-(SW2-PadCH2B)") (class "Default")
      (node (ref "SW2") (pin "CH2B") (pinfunction "CH2B_CH2B") (pintype "bidirectional"))
    )
    (net (code "137") (name "unconnected-(SW2-PadCOM2)") (class "Default")
      (node (ref "SW2") (pin "COM2") (pinfunction "COM2_COM2") (pintype "bidirectional"))
    )
    (net (code "138") (name "unconnected-(SW3-PadCH2A)") (class "Default")
      (node (ref "SW3") (pin "CH2A") (pinfunction "CH2A_CH2A") (pintype "bidirectional"))
    )
    (net (code "139") (name "unconnected-(SW3-PadCH2B)") (class "Default")
      (node (ref "SW3") (pin "CH2B") (pinfunction "CH2B_CH2B") (pintype "bidirectional"))
    )
    (net (code "140") (name "unconnected-(SW3-PadCOM2)") (class "Default")
      (node (ref "SW3") (pin "COM2") (pinfunction "COM2_COM2") (pintype "bidirectional"))
    )
    (net (code "141") (name "unconnected-(SW4-PadCH2A)") (class "Default")
      (node (ref "SW4") (pin "CH2A") (pinfunction "CH2A_CH2A") (pintype "bidirectional"))
    )
    (net (code "142") (name "unconnected-(SW4-PadCH2B)") (class "Default")
      (node (ref "SW4") (pin "CH2B") (pinfunction "CH2B_CH2B") (pintype "bidirectional"))
    )
    (net (code "143") (name "unconnected-(SW4-PadCOM2)") (class "Default")
      (node (ref "SW4") (pin "COM2") (pinfunction "COM2_COM2") (pintype "bidirectional"))
    )
    (net (code "144") (name "unconnected-(SW5-PadCH1A)") (class "Default")
      (node (ref "SW5") (pin "CH1A") (pinfunction "CH1A_CH1A") (pintype "bidirectional"))
    )
    (net (code "145") (name "unconnected-(SW5-PadCH2A)") (class "Default")
      (node (ref "SW5") (pin "CH2A") (pinfunction "CH2A_CH2A") (pintype "bidirectional"))
    )
    (net (code "146") (name "unconnected-(SW6-PadCH1B)") (class "Default")
      (node (ref "SW6") (pin "CH1B") (pinfunction "CH1B_CH1B") (pintype "bidirectional"))
    )
    (net (code "147") (name "unconnected-(SW6-PadCH2B)") (class "Default")
      (node (ref "SW6") (pin "CH2B") (pinfunction "CH2B_CH2B") (pintype "bidirectional"))
    )
    (net (code "148") (name "unconnected-(SW7-PadCH2A)") (class "Default")
      (node (ref "SW7") (pin "CH2A") (pinfunction "CH2A_CH2A") (pintype "bidirectional"))
    )
    (net (code "149") (name "unconnected-(SW7-PadCH2B)") (class "Default")
      (node (ref "SW7") (pin "CH2B") (pinfunction "CH2B_CH2B") (pintype "bidirectional"))
    )
    (net (code "150") (name "unconnected-(SW7-PadCOM2)") (class "Default")
      (node (ref "SW7") (pin "COM2") (pinfunction "COM2_COM2") (pintype "bidirectional"))
    )
    (net (code "151") (name "unconnected-(U$1-Pad32)") (class "Default")
      (node (ref "U$1") (pin "32") (pinfunction "32_32") (pintype "bidirectional"))
    )
    (net (code "152") (name "unconnected-(U$1-PadAREF)") (class "Default")
      (node (ref "U$1") (pin "AREF") (pinfunction "AREF_AREF") (pintype "bidirectional"))
    )
    (net (code "153") (name "unconnected-(U$5-NC-PadP$6)") (class "Default")
      (node (ref "U$5") (pin "P$6") (pinfunction "NC_P$6") (pintype "bidirectional"))
    )
    (net (code "154") (name "unconnected-(U$8-TD-Pad4)") (class "Default")
      (node (ref "U$8") (pin "4") (pinfunction "TD_4") (pintype "bidirectional"))
    )
    (net (code "155") (name "unconnected-(U$13-ALERT-Pad2)") (class "Default")
      (node (ref "U$13") (pin "2") (pinfunction "ALERT_2") (pintype "output"))
    )
    (net (code "156") (name "unconnected-(U$14-GPIO1-Pad5)") (class "Default")
      (node (ref "U$14") (pin "5") (pinfunction "GPIO1_5") (pintype "bidirectional"))
    )
    (net (code "157") (name "unconnected-(U$14-XSHUT-Pad6)") (class "Default")
      (node (ref "U$14") (pin "6") (pinfunction "XSHUT_6") (pintype "bidirectional"))
    )
    (net (code "158") (name "unconnected-(U$15-DRDY-Pad5)") (class "Default")
      (node (ref "U$15") (pin "5") (pinfunction "DRDY_5") (pintype "bidirectional"))
    )
    (net (code "159") (name "unconnected-(U$21-OSCIO-Pad11)") (class "Default")
      (node (ref "U$21") (pin "11") (pinfunction "OSCIO_11") (pintype "bidirectional"))
    )
    (net (code "160") (name "unconnected-(U$23-EN-Pad6)") (class "Default")
      (node (ref "U$23") (pin "6") (pinfunction "EN_6") (pintype "bidirectional"))
    )
    (net (code "161") (name "unconnected-(U$23-STATE-Pad1)") (class "Default")
      (node (ref "U$23") (pin "1") (pinfunction "STATE_1") (pintype "bidirectional"))
    )
    (net (code "162") (name "unconnected-(U1-USBID-PadID1)") (class "Default")
      (node (ref "U1") (pin "ID1") (pinfunction "USBID_ID1") (pintype "bidirectional"))
    )
    (net (code "163") (name "unconnected-(U3-PadADO)") (class "Default")
      (node (ref "U3") (pin "ADO") (pinfunction "ADO_ADO") (pintype "bidirectional"))
    )
    (net (code "164") (name "unconnected-(U3-PadINT)") (class "Default")
      (node (ref "U3") (pin "INT") (pinfunction "INT_INT") (pintype "bidirectional"))
    )
    (net (code "165") (name "unconnected-(U3-PadXCL)") (class "Default")
      (node (ref "U3") (pin "XCL") (pinfunction "XCL_XCL") (pintype "bidirectional"))
    )
    (net (code "166") (name "unconnected-(U3-PadXDA)") (class "Default")
      (node (ref "U3") (pin "XDA") (pinfunction "XDA_XDA") (pintype "bidirectional"))
    )
  )
)
